# ES_Daisy_Seed2_DFM_EVAL_EURO_Rev2.net
KiCad netlist of a schematic drawn in EAGLE
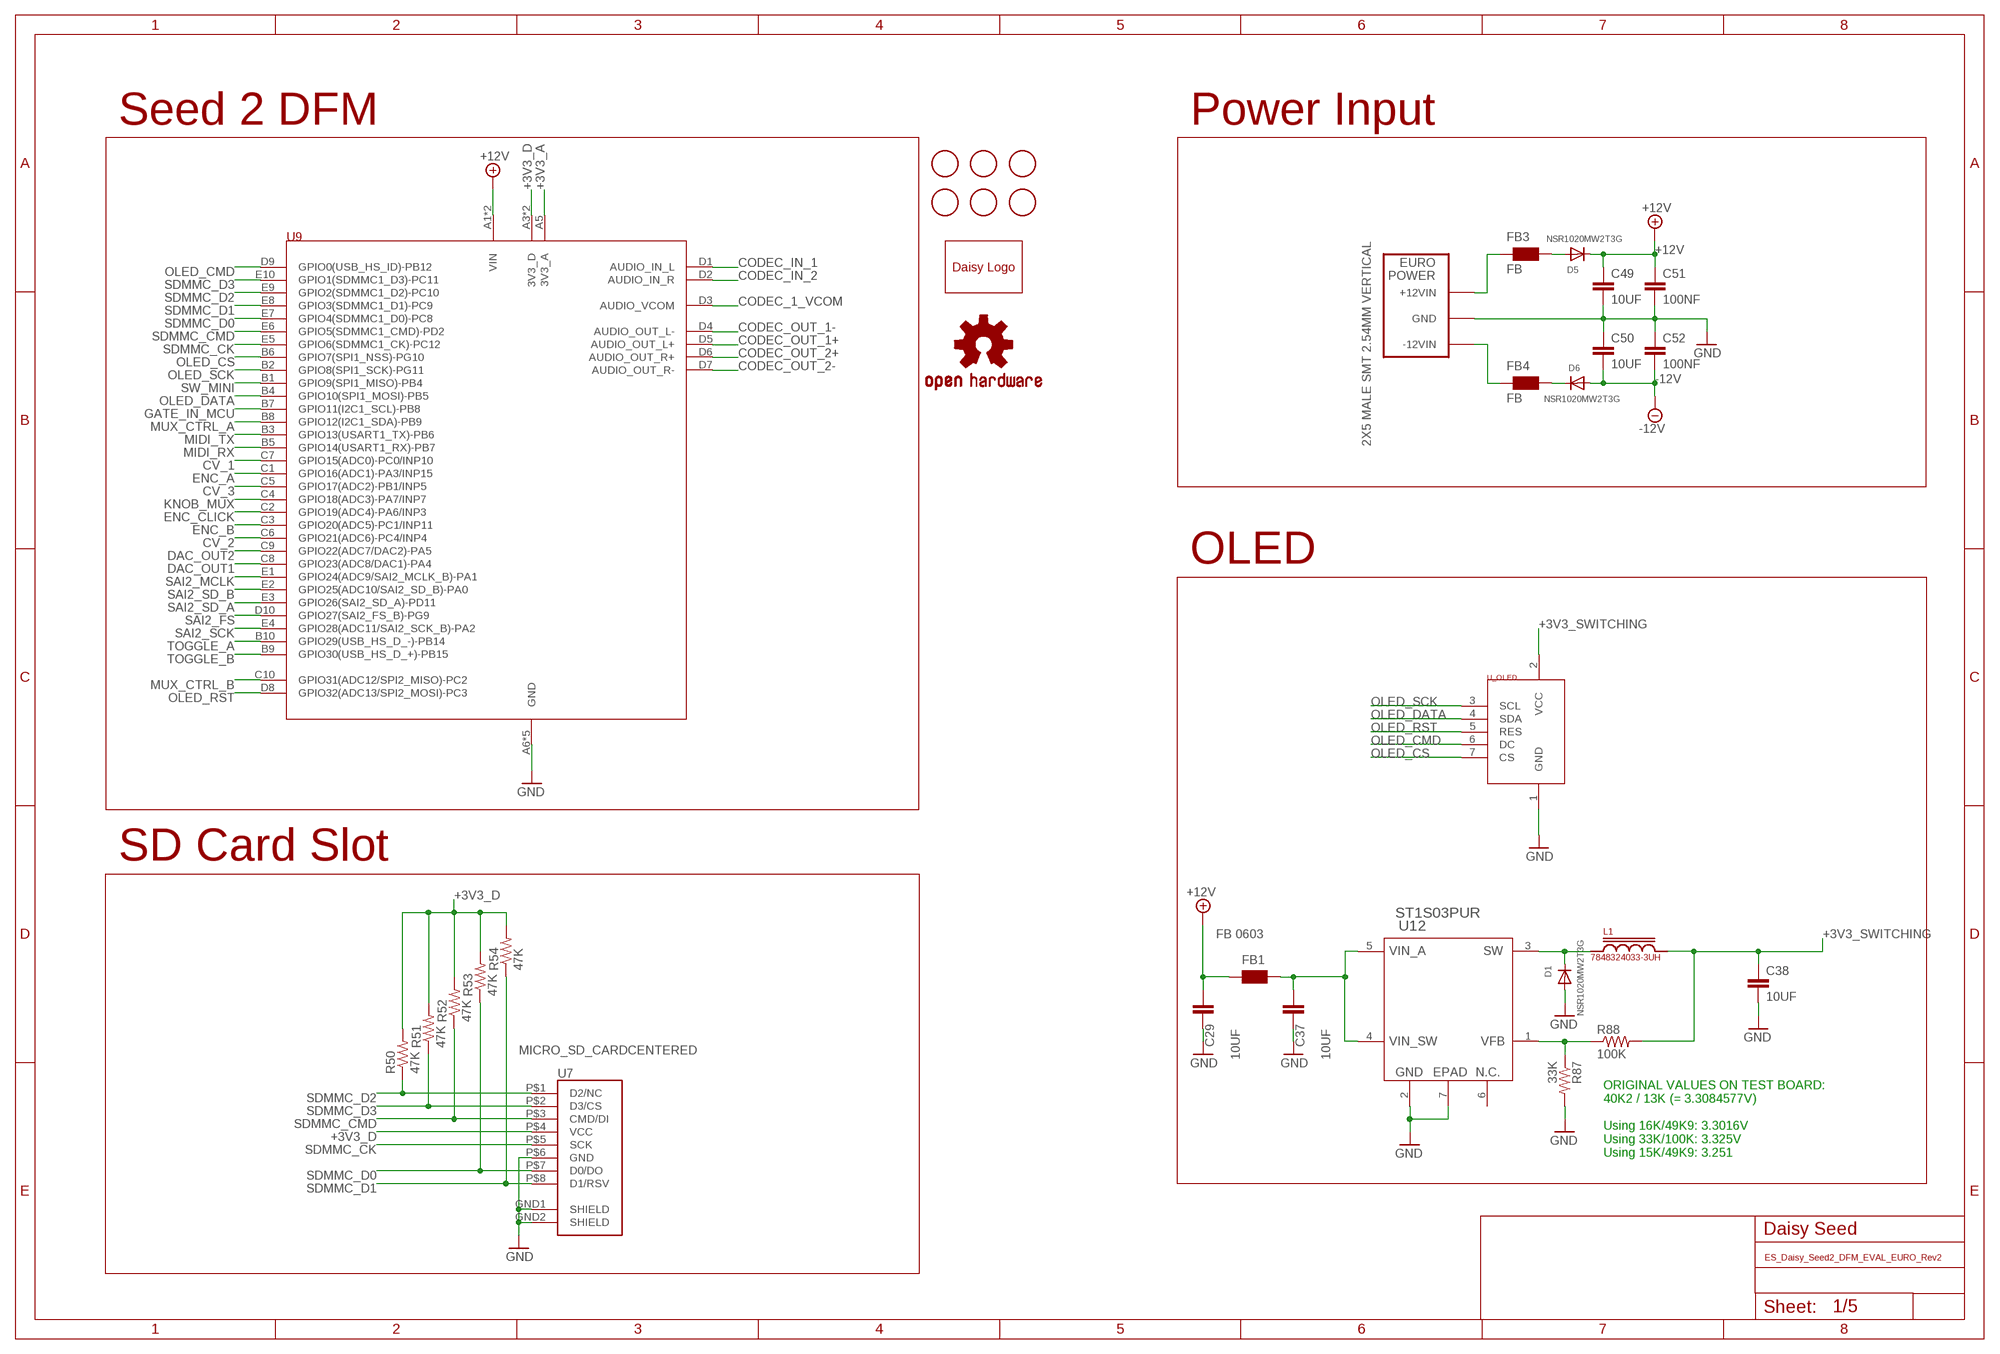
[diagram p0: schematic, sheet 1]
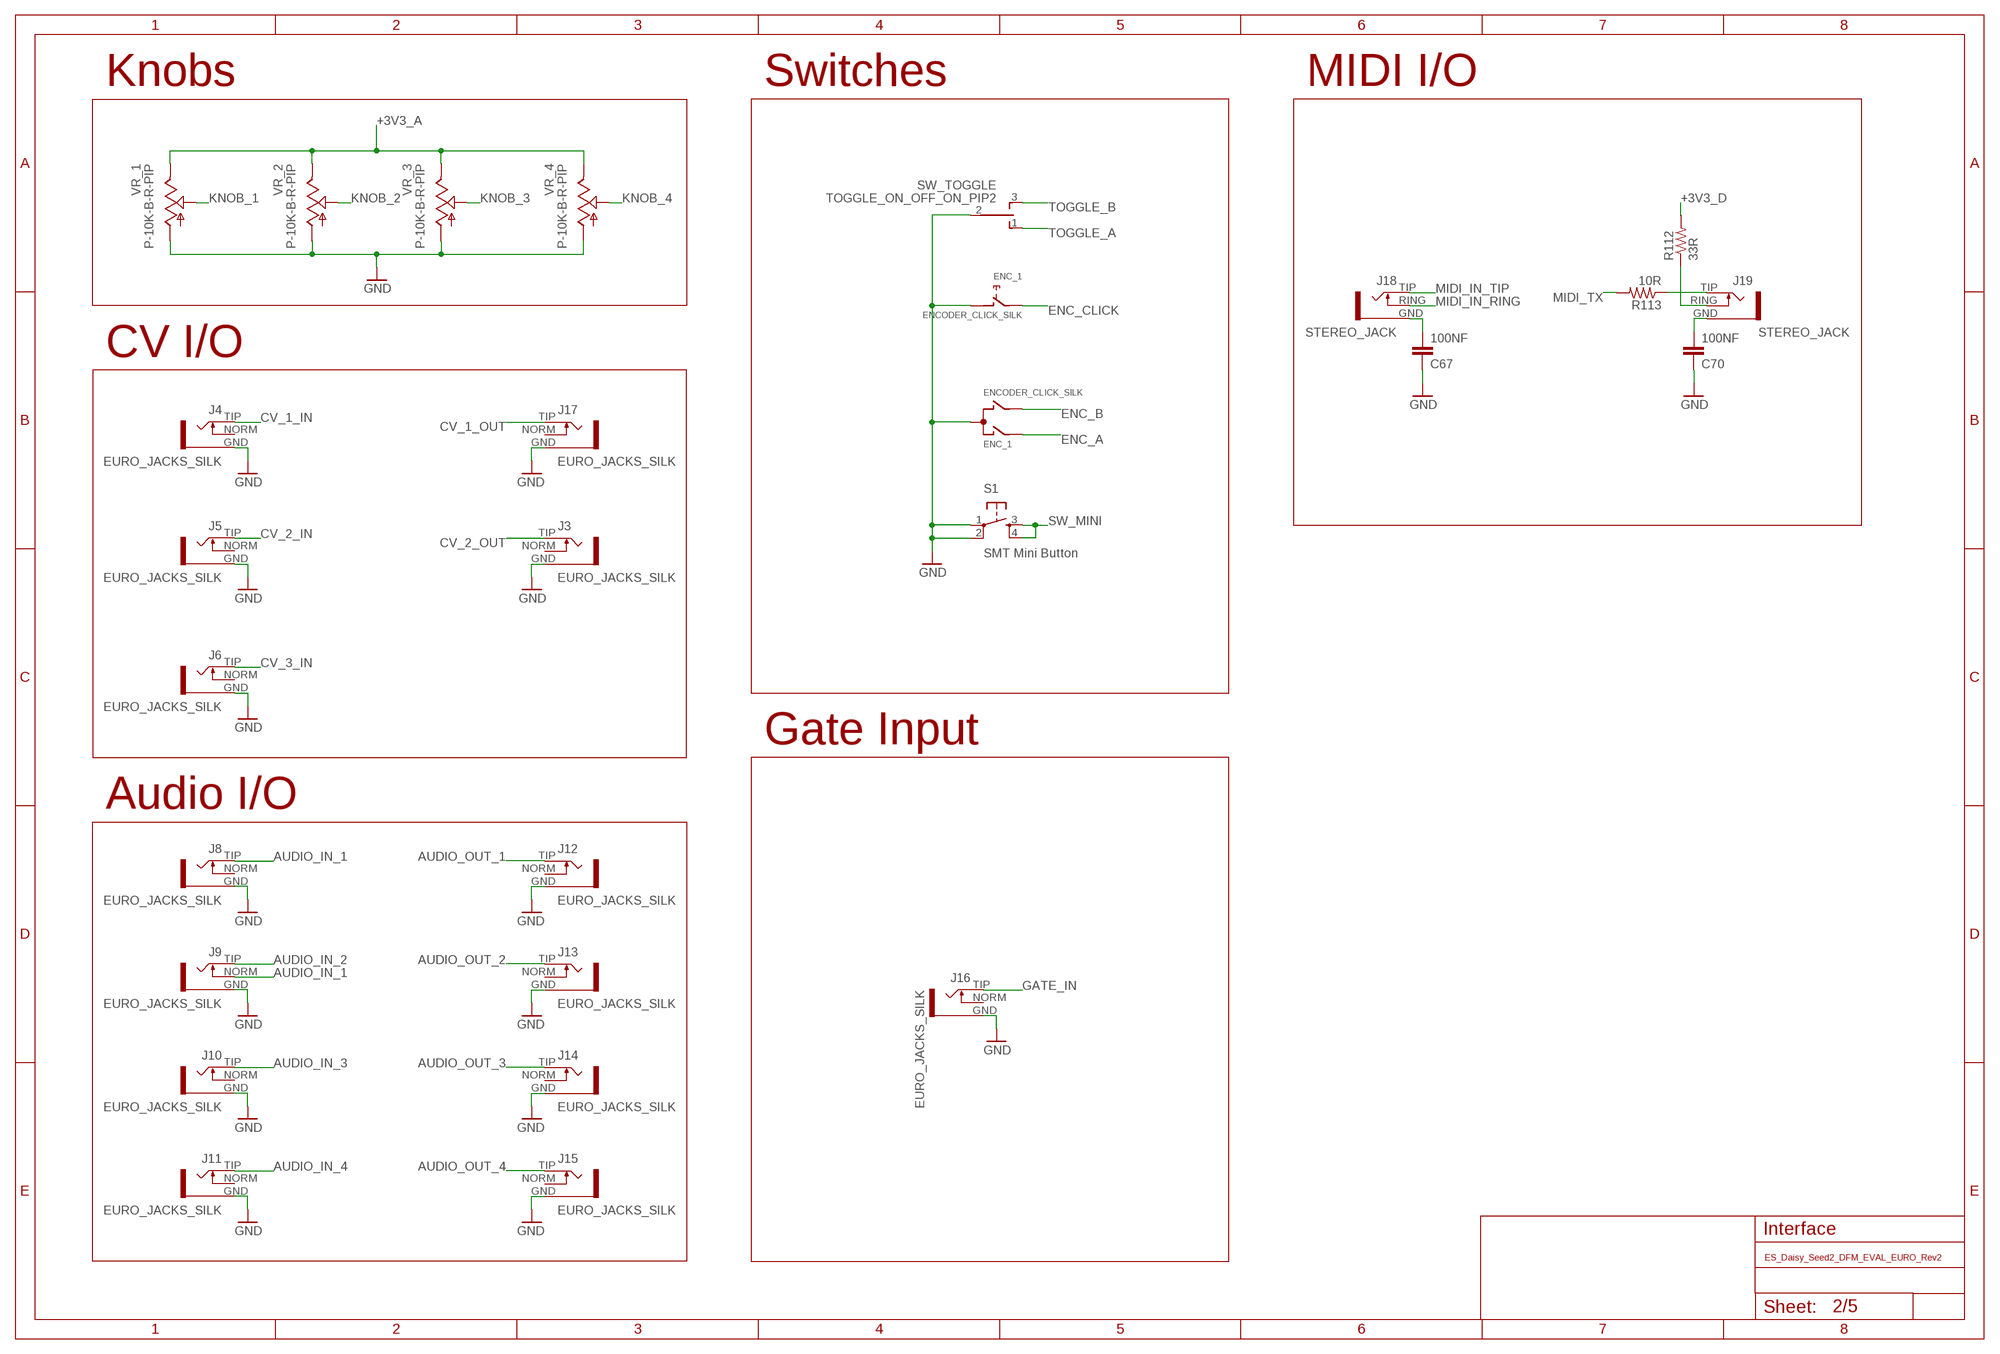
[diagram p1: schematic, sheet 2]
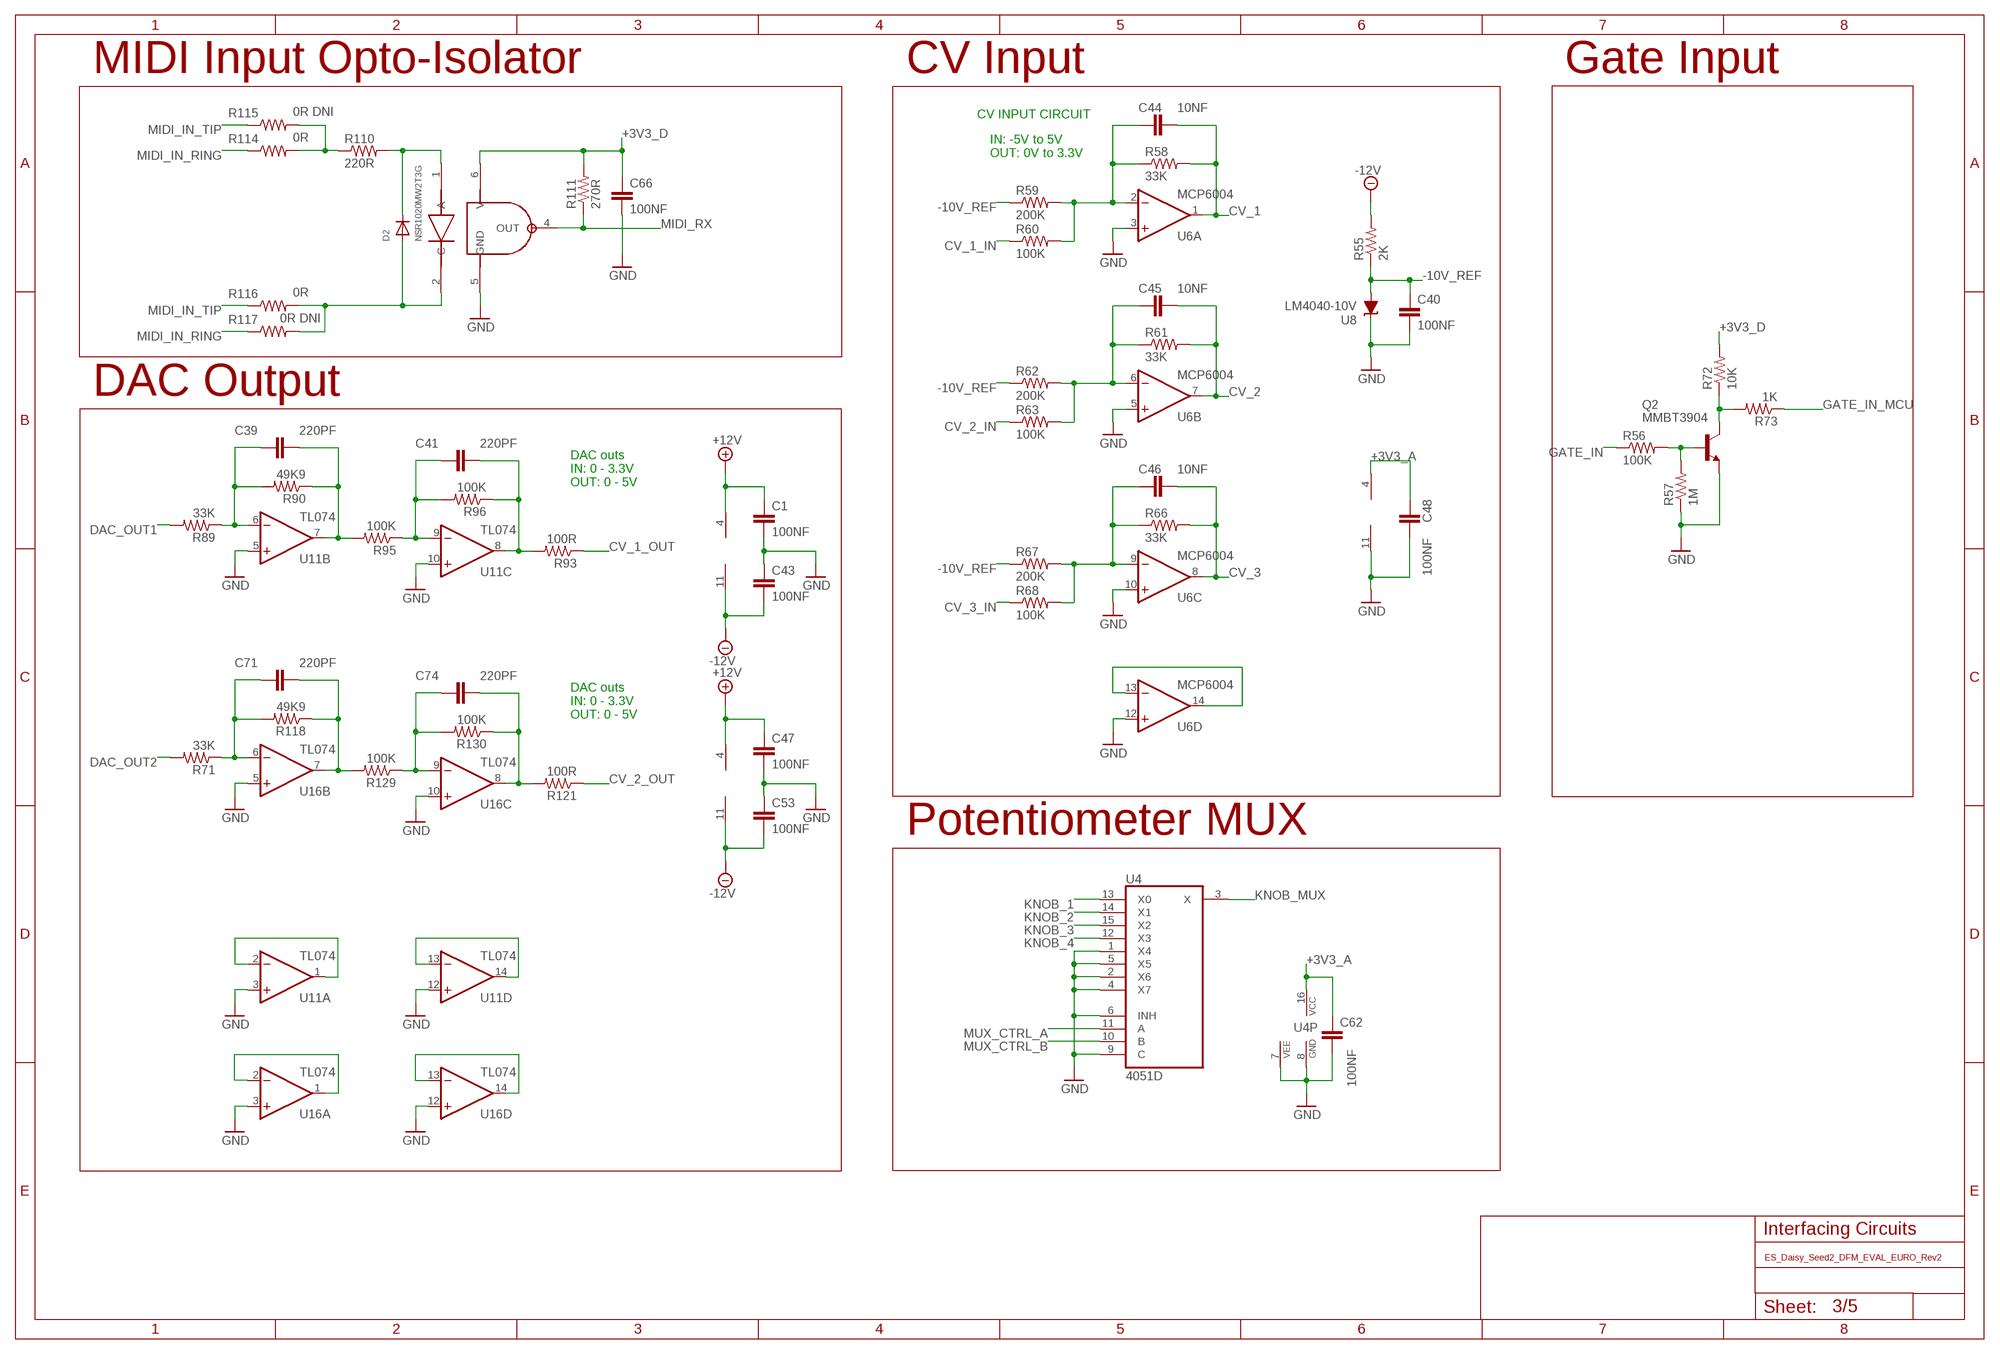
[diagram p2: schematic, sheet 3]
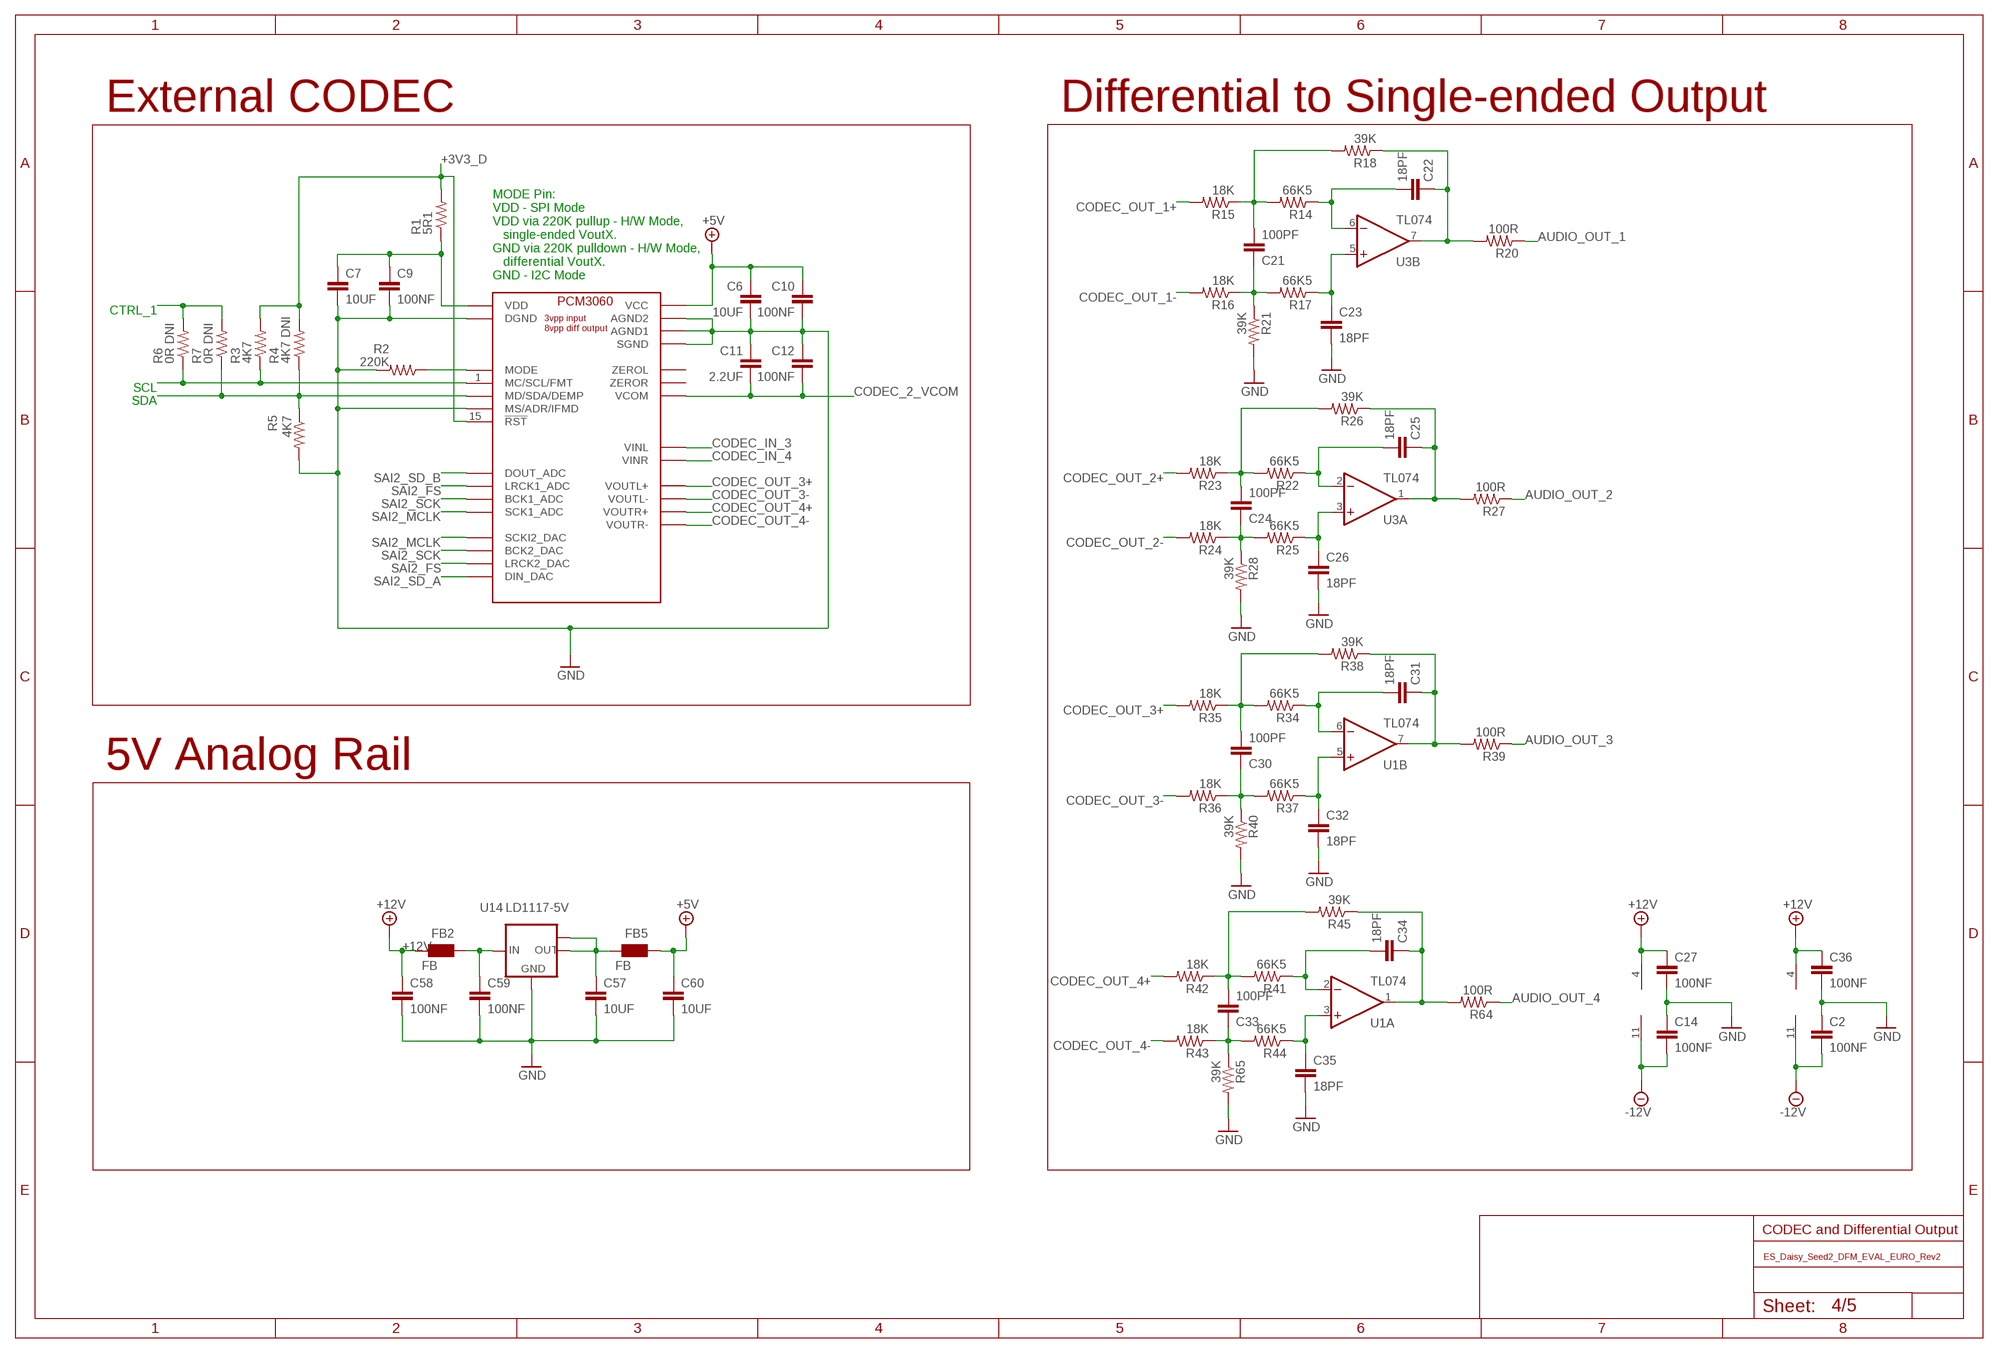
[diagram p3: schematic, sheet 4]
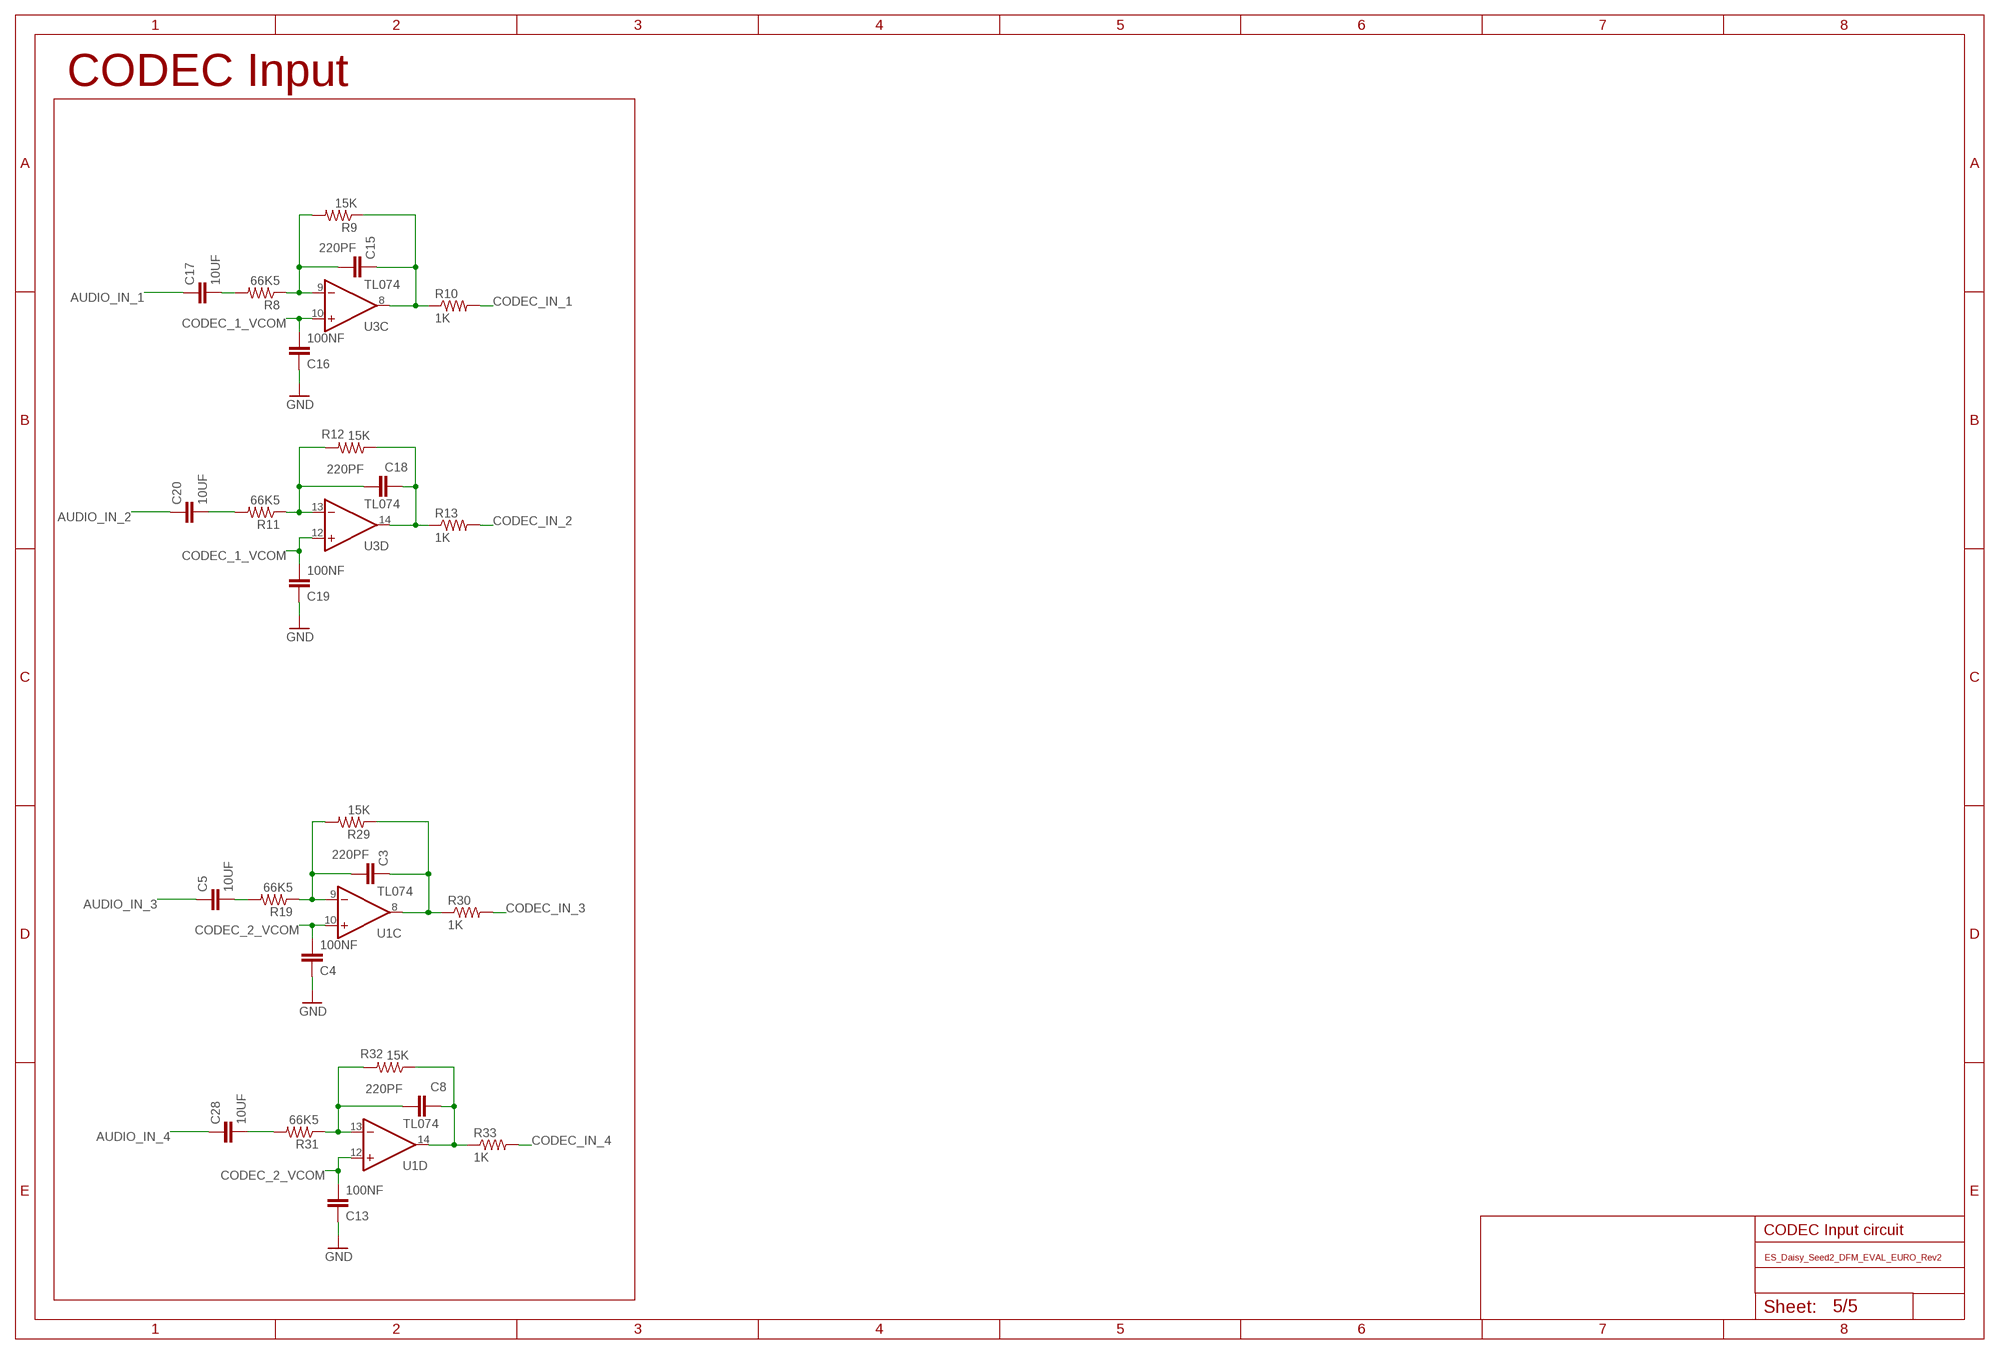
[diagram p4: schematic, sheet 5]

(export (version "E")
  (design (tool "Eeschema 10.0.6"))
  (components
    (comp (ref "C1")
      (value "100NF")
      (footprint "eagle-import:C0402")
      (libsource (lib "eagle-import") (part "C-EUC0402"))
    )
    (comp (ref "C39")
      (value "220PF")
      (footprint "eagle-import:C0603")
      (libsource (lib "eagle-import") (part "C-EUC0603"))
    )
    (comp (ref "C40")
      (value "100NF")
      (footprint "eagle-import:C0402")
      (libsource (lib "eagle-import") (part "C-EUC0402"))
    )
    (comp (ref "C41")
      (value "220PF")
      (footprint "eagle-import:C0603")
      (libsource (lib "eagle-import") (part "C-EUC0603"))
    )
    (comp (ref "C43")
      (value "100NF")
      (footprint "eagle-import:C0402")
      (libsource (lib "eagle-import") (part "C-EUC0402"))
    )
    (comp (ref "C44")
      (value "10NF")
      (footprint "eagle-import:C0603")
      (libsource (lib "eagle-import") (part "C-EUC0603"))
    )
    (comp (ref "C45")
      (value "10NF")
      (footprint "eagle-import:C0603")
      (libsource (lib "eagle-import") (part "C-EUC0603"))
    )
    (comp (ref "C46")
      (value "10NF")
      (footprint "eagle-import:C0603")
      (libsource (lib "eagle-import") (part "C-EUC0603"))
    )
    (comp (ref "C47")
      (value "100NF")
      (footprint "eagle-import:C0402")
      (libsource (lib "eagle-import") (part "C-EUC0402"))
    )
    (comp (ref "C48")
      (value "100NF")
      (footprint "eagle-import:C0402")
      (libsource (lib "eagle-import") (part "C-EUC0402"))
    )
    (comp (ref "C53")
      (value "100NF")
      (footprint "eagle-import:C0402")
      (libsource (lib "eagle-import") (part "C-EUC0402"))
    )
    (comp (ref "C62")
      (value "100NF")
      (footprint "eagle-import:C0402")
      (libsource (lib "eagle-import") (part "C-EUC0402"))
    )
    (comp (ref "C66")
      (value "100NF")
      (footprint "eagle-import:C0402")
      (libsource (lib "eagle-import") (part "C-EUC0402"))
    )
    (comp (ref "C71")
      (value "220PF")
      (footprint "eagle-import:C0603")
      (libsource (lib "eagle-import") (part "C-EUC0603"))
    )
    (comp (ref "C74")
      (value "220PF")
      (footprint "eagle-import:C0603")
      (libsource (lib "eagle-import") (part "C-EUC0603"))
    )
    (comp (ref "D2")
      (value "NSR1020MW2T3G")
      (footprint "eagle-import:SOD-323F")
      (libsource (lib "eagle-import") (part "DIODE_SOD-323F"))
    )
    (comp (ref "Q2")
      (value "MMBT3904")
      (footprint "eagle-import:SOT23-BEC")
      (libsource (lib "eagle-import") (part "NPNSOT23-BEC"))
    )
    (comp (ref "R55")
      (value "2K")
      (footprint "eagle-import:R0603")
      (libsource (lib "eagle-import") (part "R-US_R0603"))
    )
    (comp (ref "R56")
      (value "100K")
      (footprint "eagle-import:R0402")
      (libsource (lib "eagle-import") (part "R-US_R0402"))
    )
    (comp (ref "R57")
      (value "1M")
      (footprint "eagle-import:R0603")
      (libsource (lib "eagle-import") (part "R-US_R0603"))
    )
    (comp (ref "R58")
      (value "33K")
      (footprint "eagle-import:R0603")
      (libsource (lib "eagle-import") (part "R-US_R0603"))
    )
    (comp (ref "R59")
      (value "200K")
      (footprint "eagle-import:R0603")
      (libsource (lib "eagle-import") (part "R-US_R0603"))
    )
    (comp (ref "R60")
      (value "100K")
      (footprint "eagle-import:R0402")
      (libsource (lib "eagle-import") (part "R-US_R0402"))
    )
    (comp (ref "R61")
      (value "33K")
      (footprint "eagle-import:R0603")
      (libsource (lib "eagle-import") (part "R-US_R0603"))
    )
    (comp (ref "R62")
      (value "200K")
      (footprint "eagle-import:R0603")
      (libsource (lib "eagle-import") (part "R-US_R0603"))
    )
    (comp (ref "R63")
      (value "100K")
      (footprint "eagle-import:R0402")
      (libsource (lib "eagle-import") (part "R-US_R0402"))
    )
    (comp (ref "R66")
      (value "33K")
      (footprint "eagle-import:R0603")
      (libsource (lib "eagle-import") (part "R-US_R0603"))
    )
    (comp (ref "R67")
      (value "200K")
      (footprint "eagle-import:R0603")
      (libsource (lib "eagle-import") (part "R-US_R0603"))
    )
    (comp (ref "R68")
      (value "100K")
      (footprint "eagle-import:R0402")
      (libsource (lib "eagle-import") (part "R-US_R0402"))
    )
    (comp (ref "R71")
      (value "33K")
      (footprint "eagle-import:R0603")
      (libsource (lib "eagle-import") (part "R-US_R0603"))
    )
    (comp (ref "R72")
      (value "10K")
      (footprint "eagle-import:R0603")
      (libsource (lib "eagle-import") (part "R-US_R0603"))
    )
    (comp (ref "R73")
      (value "1K")
      (footprint "eagle-import:R0402")
      (libsource (lib "eagle-import") (part "R-US_R0402"))
    )
    (comp (ref "R89")
      (value "33K")
      (footprint "eagle-import:R0603")
      (libsource (lib "eagle-import") (part "R-US_R0603"))
    )
    (comp (ref "R90")
      (value "49K9")
      (footprint "eagle-import:R0603")
      (libsource (lib "eagle-import") (part "R-US_R0603"))
    )
    (comp (ref "R93")
      (value "100R")
      (footprint "eagle-import:R0603")
      (libsource (lib "eagle-import") (part "R-US_R0603"))
    )
    (comp (ref "R95")
      (value "100K")
      (footprint "eagle-import:R0402")
      (libsource (lib "eagle-import") (part "R-US_R0402"))
    )
    (comp (ref "R96")
      (value "100K")
      (footprint "eagle-import:R0402")
      (libsource (lib "eagle-import") (part "R-US_R0402"))
    )
    (comp (ref "R110")
      (value "220R")
      (footprint "eagle-import:R0603")
      (libsource (lib "eagle-import") (part "R-US_R0603"))
    )
    (comp (ref "R111")
      (value "270R")
      (footprint "eagle-import:R0603")
      (libsource (lib "eagle-import") (part "R-US_R0603"))
    )
    (comp (ref "R114")
      (value "0R")
      (footprint "eagle-import:R0603")
      (libsource (lib "eagle-import") (part "R-US_R0603"))
    )
    (comp (ref "R115")
      (value "0R DNI")
      (footprint "eagle-import:R0603")
      (libsource (lib "eagle-import") (part "R-US_R0603"))
    )
    (comp (ref "R116")
      (value "0R")
      (footprint "eagle-import:R0603")
      (libsource (lib "eagle-import") (part "R-US_R0603"))
    )
    (comp (ref "R117")
      (value "0R DNI")
      (footprint "eagle-import:R0603")
      (libsource (lib "eagle-import") (part "R-US_R0603"))
    )
    (comp (ref "R118")
      (value "49K9")
      (footprint "eagle-import:R0603")
      (libsource (lib "eagle-import") (part "R-US_R0603"))
    )
    (comp (ref "R121")
      (value "100R")
      (footprint "eagle-import:R0603")
      (libsource (lib "eagle-import") (part "R-US_R0603"))
    )
    (comp (ref "R129")
      (value "100K")
      (footprint "eagle-import:R0402")
      (libsource (lib "eagle-import") (part "R-US_R0402"))
    )
    (comp (ref "R130")
      (value "100K")
      (footprint "eagle-import:R0402")
      (libsource (lib "eagle-import") (part "R-US_R0402"))
    )
    (comp (ref "U4")
      (value "4051D")
      (footprint "eagle-import:SO-16")
      (libsource (lib "eagle-import") (part "4051D"))
    )
    (comp (ref "U6")
      (value "MCP6004")
      (footprint "eagle-import:TSSOP-14")
      (fields (field (name "MPN") "MCP6004T-E/ST"))
      (libsource (lib "eagle-import") (part "MCP6004_TSSOP-14"))
    )
    (comp (ref "U8")
      (value "LM4040-10V")
      (footprint "eagle-import:DBZ_R-PDSO-G3")
      (fields (field (name "MPN") "LM4041A12IDBZR"))
      (libsource (lib "eagle-import") (part "LM4040-10VDBZA12"))
    )
    (comp (ref "U11")
      (value "TL074")
      (footprint "eagle-import:TSSOP-14")
      (fields (field (name "MPN") "TL074CPWR"))
      (libsource (lib "eagle-import") (part "TL074_TSSOP-14"))
    )
    (comp (ref "U15")
      (value "OPTOISOLATOR_H11L1M")
      (footprint "eagle-import:DIL06_GULLWING")
      (fields (field (name "MPN") "H11L1SR2M"))
      (libsource (lib "eagle-import") (part "OPTOISOLATOR_H11L1M"))
    )
    (comp (ref "U16")
      (value "TL074")
      (footprint "eagle-import:TSSOP-14")
      (fields (field (name "MPN") "TL074CPWR"))
      (libsource (lib "eagle-import") (part "TL074_TSSOP-14"))
    )
    (comp (ref "C29")
      (value "10UF")
      (footprint "eagle-import:C0805")
      (libsource (lib "eagle-import") (part "C-EUC0805"))
    )
    (comp (ref "C37")
      (value "10UF")
      (footprint "eagle-import:C0805")
      (libsource (lib "eagle-import") (part "Electrosmith-Passives_29888544_C-EUC0805"))
    )
    (comp (ref "C38")
      (value "10UF")
      (footprint "eagle-import:C0805")
      (libsource (lib "eagle-import") (part "C-EUC0805"))
    )
    (comp (ref "C49")
      (value "10UF")
      (footprint "eagle-import:C0805")
      (libsource (lib "eagle-import") (part "C-EUC0805"))
    )
    (comp (ref "C50")
      (value "10UF")
      (footprint "eagle-import:C0805")
      (libsource (lib "eagle-import") (part "C-EUC0805"))
    )
    (comp (ref "C51")
      (value "100NF")
      (footprint "eagle-import:C0402")
      (libsource (lib "eagle-import") (part "C-EUC0402"))
    )
    (comp (ref "C52")
      (value "100NF")
      (footprint "eagle-import:C0402")
      (libsource (lib "eagle-import") (part "C-EUC0402"))
    )
    (comp (ref "D1")
      (value "NSR1020MW2T3G")
      (footprint "eagle-import:SOD-323F")
      (libsource (lib "eagle-import") (part "Electrosmith-Semiconductors_29887508_DIODE_SOD-323F"))
    )
    (comp (ref "D5")
      (value "NSR1020MW2T3G")
      (footprint "eagle-import:SOD-323F")
      (libsource (lib "eagle-import") (part "DIODE_SOD-323F"))
    )
    (comp (ref "D6")
      (value "NSR1020MW2T3G")
      (footprint "eagle-import:SOD-323F")
      (libsource (lib "eagle-import") (part "DIODE_SOD-323F"))
    )
    (comp (ref "FB1")
      (value "FB 0603")
      (footprint "eagle-import:WUERTH-ELEKTRONIK_0603")
      (libsource (lib "eagle-import") (part "FERRITE_BEAD_0603"))
    )
    (comp (ref "FB3")
      (value "FB")
      (footprint "eagle-import:WUERTH-ELEKTRONIK_0603")
      (libsource (lib "eagle-import") (part "FERRITE_BEAD_0603"))
    )
    (comp (ref "FB4")
      (value "FB")
      (footprint "eagle-import:WUERTH-ELEKTRONIK_0603")
      (libsource (lib "eagle-import") (part "FERRITE_BEAD_0603"))
    )
    (comp (ref "FD1")
      (value "FIDUCIAL")
      (footprint "eagle-import:FIDUCIAL_1MM")
      (libsource (lib "eagle-import") (part "FIDUCIAL"))
    )
    (comp (ref "FD2")
      (value "FIDUCIAL")
      (footprint "eagle-import:FIDUCIAL_1MM")
      (libsource (lib "eagle-import") (part "FIDUCIAL"))
    )
    (comp (ref "FD3")
      (value "FIDUCIAL")
      (footprint "eagle-import:FIDUCIAL_1MM")
      (libsource (lib "eagle-import") (part "FIDUCIAL"))
    )
    (comp (ref "FD4")
      (value "FIDUCIAL")
      (footprint "eagle-import:FIDUCIAL_1MM")
      (libsource (lib "eagle-import") (part "FIDUCIAL"))
    )
    (comp (ref "FD5")
      (value "FIDUCIAL")
      (footprint "eagle-import:FIDUCIAL_1MM")
      (libsource (lib "eagle-import") (part "FIDUCIAL"))
    )
    (comp (ref "FD6")
      (value "FIDUCIAL")
      (footprint "eagle-import:FIDUCIAL_1MM")
      (libsource (lib "eagle-import") (part "FIDUCIAL"))
    )
    (comp (ref "L1")
      (value "7848324033-3UH")
      (footprint "eagle-import:I1008")
      (fields (field (name "MPN") "AIML-1008HC-3R3M-T"))
      (libsource (lib "eagle-import") (part "INDUCTOR1008"))
    )
    (comp (ref "LOGO1")
      (value "OSHW-LOGO")
      (footprint "eagle-import:OSHW-LOGO-L_TEXT")
      (libsource (lib "eagle-import") (part "OSHW-LOGO"))
    )
    (comp (ref "P1")
      (value "2X5 MALE SMT 2.54MM VERTICAL")
      (footprint "eagle-import:EURORACK_POWER_SMT")
      (fields (field (name "MANF") "FCI") (field (name "MPN") "PH2-10-MTA-SMT-PP-T/R"))
      (libsource (lib "eagle-import") (part "EURORACK_POWERSMT"))
    )
    (comp (ref "R50")
      (value "47K")
      (footprint "eagle-import:R0603")
      (libsource (lib "eagle-import") (part "R-US_R0603"))
    )
    (comp (ref "R51")
      (value "47K")
      (footprint "eagle-import:R0603")
      (libsource (lib "eagle-import") (part "R-US_R0603"))
    )
    (comp (ref "R52")
      (value "47K")
      (footprint "eagle-import:R0603")
      (libsource (lib "eagle-import") (part "R-US_R0603"))
    )
    (comp (ref "R53")
      (value "47K")
      (footprint "eagle-import:R0603")
      (libsource (lib "eagle-import") (part "R-US_R0603"))
    )
    (comp (ref "R54")
      (value "47K")
      (footprint "eagle-import:R0603")
      (libsource (lib "eagle-import") (part "R-US_R0603"))
    )
    (comp (ref "R87")
      (value "33K")
      (footprint "eagle-import:R0603")
      (libsource (lib "eagle-import") (part "R-US_R0603"))
    )
    (comp (ref "R88")
      (value "100K")
      (footprint "eagle-import:R0402")
      (libsource (lib "eagle-import") (part "R-US_R0402"))
    )
    (comp (ref "U$5")
      (value "DAISYLOGO")
      (footprint "eagle-import:ES_DAISY_LOGO_1")
      (libsource (lib "eagle-import") (part "DAISYLOGO"))
    )
    (comp (ref "U7")
      (value "MICRO_SD_CARDCENTERED")
      (footprint "eagle-import:VERT_MICROSD_CENTERED")
      (libsource (lib "eagle-import") (part "MICRO_SD_CARDCENTERED"))
    )
    (comp (ref "U9")
      (value "ES_DAISY_SEED2_DFM_REV1\"\"")
      (footprint "eagle-import:ES_DAISY_SEED2_DFM_REV1")
      (libsource (lib "eagle-import") (part "ES_DAISY_SEED2_DFM_REV1{dblquote}{dblquote}"))
    )
    (comp (ref "U12")
      (value "ST1S03PUR")
      (footprint "eagle-import:DFN06_3X3_STM")
      (fields (field (name "COPYRIGHT") "Copyright (C) 2021 Ultra Librarian. All rights reserved."))
      (libsource (lib "eagle-import") (part "ST1S03PUR"))
    )
    (comp (ref "U_OLED")
      (value "OLED_DISPLAY")
      (footprint "eagle-import:ER-OLEDM015-2")
      (fields (field (name "MPN") "ER-OLEDM015-2W-SPI-I2C"))
      (libsource (lib "eagle-import") (part "OLED_DISPLAY"))
    )
    (comp (ref "C67")
      (value "100NF")
      (footprint "eagle-import:C0402")
      (libsource (lib "eagle-import") (part "C-EUC0402"))
    )
    (comp (ref "C70")
      (value "100NF")
      (footprint "eagle-import:C0402")
      (libsource (lib "eagle-import") (part "C-EUC0402"))
    )
    (comp (ref "ENC_1")
      (value "ENCODER_CLICK_SILK")
      (footprint "eagle-import:PEC11_SILK")
      (libsource (lib "eagle-import") (part "ENCODERSILK_CLICK_"))
    )
    (comp (ref "J3")
      (value "EURO_JACKS_SILK")
      (footprint "eagle-import:S_JACK_SILK")
      (libsource (lib "eagle-import") (part "EURO_JACKS_SILK"))
    )
    (comp (ref "J4")
      (value "EURO_JACKS_SILK")
      (footprint "eagle-import:S_JACK_SILK")
      (libsource (lib "eagle-import") (part "EURO_JACKS_SILK"))
    )
    (comp (ref "J5")
      (value "EURO_JACKS_SILK")
      (footprint "eagle-import:S_JACK_SILK")
      (libsource (lib "eagle-import") (part "EURO_JACKS_SILK"))
    )
    (comp (ref "J6")
      (value "EURO_JACKS_SILK")
      (footprint "eagle-import:S_JACK_SILK")
      (libsource (lib "eagle-import") (part "EURO_JACKS_SILK"))
    )
    (comp (ref "J8")
      (value "EURO_JACKS_SILK")
      (footprint "eagle-import:S_JACK_SILK")
      (libsource (lib "eagle-import") (part "EURO_JACKS_SILK"))
    )
    (comp (ref "J9")
      (value "EURO_JACKS_SILK")
      (footprint "eagle-import:S_JACK_SILK")
      (libsource (lib "eagle-import") (part "EURO_JACKS_SILK"))
    )
    (comp (ref "J10")
      (value "EURO_JACKS_SILK")
      (footprint "eagle-import:S_JACK_SILK")
      (libsource (lib "eagle-import") (part "EURO_JACKS_SILK"))
    )
    (comp (ref "J11")
      (value "EURO_JACKS_SILK")
      (footprint "eagle-import:S_JACK_SILK")
      (libsource (lib "eagle-import") (part "EURO_JACKS_SILK"))
    )
    (comp (ref "J12")
      (value "EURO_JACKS_SILK")
      (footprint "eagle-import:S_JACK_SILK")
      (libsource (lib "eagle-import") (part "EURO_JACKS_SILK"))
    )
    (comp (ref "J13")
      (value "EURO_JACKS_SILK")
      (footprint "eagle-import:S_JACK_SILK")
      (libsource (lib "eagle-import") (part "EURO_JACKS_SILK"))
    )
    (comp (ref "J14")
      (value "EURO_JACKS_SILK")
      (footprint "eagle-import:S_JACK_SILK")
      (libsource (lib "eagle-import") (part "EURO_JACKS_SILK"))
    )
    (comp (ref "J15")
      (value "EURO_JACKS_SILK")
      (footprint "eagle-import:S_JACK_SILK")
      (libsource (lib "eagle-import") (part "EURO_JACKS_SILK"))
    )
    (comp (ref "J16")
      (value "EURO_JACKS_SILK")
      (footprint "eagle-import:S_JACK_SILK")
      (libsource (lib "eagle-import") (part "EURO_JACKS_SILK"))
    )
    (comp (ref "J17")
      (value "EURO_JACKS_SILK")
      (footprint "eagle-import:S_JACK_SILK")
      (libsource (lib "eagle-import") (part "EURO_JACKS_SILK"))
    )
    (comp (ref "J18")
      (value "STEREO_JACK")
      (footprint "eagle-import:STEREO_JACK_3.5MM")
      (libsource (lib "eagle-import") (part "STEREO_JACK"))
    )
    (comp (ref "J19")
      (value "STEREO_JACK")
      (footprint "eagle-import:STEREO_JACK_3.5MM")
      (libsource (lib "eagle-import") (part "STEREO_JACK"))
    )
    (comp (ref "R112")
      (value "33R")
      (footprint "eagle-import:R0603")
      (libsource (lib "eagle-import") (part "R-US_R0603"))
    )
    (comp (ref "R113")
      (value "10R")
      (footprint "eagle-import:R0603")
      (libsource (lib "eagle-import") (part "R-US_R0603"))
    )
    (comp (ref "S1")
      (value "SMT Mini Button")
      (footprint "eagle-import:TL3301SPF160QJ")
      (fields (field (name "MPN") "TL3301SPF160QJ"))
      (libsource (lib "eagle-import") (part "TAC_SWITCH_SMT"))
    )
    (comp (ref "SW_TOGGLE")
      (value "TOGGLE_ON_OFF_ON_PIP2")
      (footprint "eagle-import:TOGGLE_SILK_PIP3")
      (libsource (lib "eagle-import") (part "TOGGLE_ON_OFF_ON_PIP2"))
    )
    (comp (ref "VR_1")
      (value "P-10K-B-R-PIP")
      (footprint "eagle-import:9MM_SNAP-IN_POT_SILK_PIP")
      (libsource (lib "eagle-import") (part "POT_9MM_SNAP-IN__SILK_PIP"))
    )
    (comp (ref "VR_2")
      (value "P-10K-B-R-PIP")
      (footprint "eagle-import:9MM_SNAP-IN_POT_SILK_PIP")
      (libsource (lib "eagle-import") (part "POT_9MM_SNAP-IN__SILK_PIP"))
    )
    (comp (ref "VR_3")
      (value "P-10K-B-R-PIP")
      (footprint "eagle-import:9MM_SNAP-IN_POT_SILK_PIP")
      (libsource (lib "eagle-import") (part "POT_9MM_SNAP-IN__SILK_PIP"))
    )
    (comp (ref "VR_4")
      (value "P-10K-B-R-PIP")
      (footprint "eagle-import:9MM_SNAP-IN_POT_SILK_PIP")
      (libsource (lib "eagle-import") (part "POT_9MM_SNAP-IN__SILK_PIP"))
    )
    (comp (ref "C3")
      (value "220PF")
      (footprint "eagle-import:C0603")
      (libsource (lib "eagle-import") (part "C-EUC0603"))
    )
    (comp (ref "C4")
      (value "100NF")
      (footprint "eagle-import:C0402")
      (libsource (lib "eagle-import") (part "C-EUC0402"))
    )
    (comp (ref "C5")
      (value "10UF")
      (footprint "eagle-import:C0805")
      (libsource (lib "eagle-import") (part "C-EUC0805"))
    )
    (comp (ref "C8")
      (value "220PF")
      (footprint "eagle-import:C0603")
      (libsource (lib "eagle-import") (part "C-EUC0603"))
    )
    (comp (ref "C13")
      (value "100NF")
      (footprint "eagle-import:C0402")
      (libsource (lib "eagle-import") (part "C-EUC0402"))
    )
    (comp (ref "C15")
      (value "220PF")
      (footprint "eagle-import:C0603")
      (libsource (lib "eagle-import") (part "C-EUC0603"))
    )
    (comp (ref "C16")
      (value "100NF")
      (footprint "eagle-import:C0402")
      (libsource (lib "eagle-import") (part "C-EUC0402"))
    )
    (comp (ref "C17")
      (value "10UF")
      (footprint "eagle-import:C0805")
      (libsource (lib "eagle-import") (part "C-EUC0805"))
    )
    (comp (ref "C18")
      (value "220PF")
      (footprint "eagle-import:C0603")
      (libsource (lib "eagle-import") (part "C-EUC0603"))
    )
    (comp (ref "C19")
      (value "100NF")
      (footprint "eagle-import:C0402")
      (libsource (lib "eagle-import") (part "C-EUC0402"))
    )
    (comp (ref "C20")
      (value "10UF")
      (footprint "eagle-import:C0805")
      (libsource (lib "eagle-import") (part "C-EUC0805"))
    )
    (comp (ref "C28")
      (value "10UF")
      (footprint "eagle-import:C0805")
      (libsource (lib "eagle-import") (part "C-EUC0805"))
    )
    (comp (ref "R8")
      (value "66K5")
      (footprint "eagle-import:R0603")
      (libsource (lib "eagle-import") (part "R-US_R0603"))
    )
    (comp (ref "R9")
      (value "15K")
      (footprint "eagle-import:R0603")
      (libsource (lib "eagle-import") (part "R-US_R0603"))
    )
    (comp (ref "R10")
      (value "1K")
      (footprint "eagle-import:R0402")
      (libsource (lib "eagle-import") (part "R-US_R0402"))
    )
    (comp (ref "R11")
      (value "66K5")
      (footprint "eagle-import:R0603")
      (libsource (lib "eagle-import") (part "R-US_R0603"))
    )
    (comp (ref "R12")
      (value "15K")
      (footprint "eagle-import:R0603")
      (libsource (lib "eagle-import") (part "R-US_R0603"))
    )
    (comp (ref "R13")
      (value "1K")
      (footprint "eagle-import:R0402")
      (libsource (lib "eagle-import") (part "R-US_R0402"))
    )
    (comp (ref "R19")
      (value "66K5")
      (footprint "eagle-import:R0603")
      (libsource (lib "eagle-import") (part "R-US_R0603"))
    )
    (comp (ref "R29")
      (value "15K")
      (footprint "eagle-import:R0603")
      (libsource (lib "eagle-import") (part "R-US_R0603"))
    )
    (comp (ref "R30")
      (value "1K")
      (footprint "eagle-import:R0402")
      (libsource (lib "eagle-import") (part "R-US_R0402"))
    )
    (comp (ref "R31")
      (value "66K5")
      (footprint "eagle-import:R0603")
      (libsource (lib "eagle-import") (part "R-US_R0603"))
    )
    (comp (ref "R32")
      (value "15K")
      (footprint "eagle-import:R0603")
      (libsource (lib "eagle-import") (part "R-US_R0603"))
    )
    (comp (ref "R33")
      (value "1K")
      (footprint "eagle-import:R0402")
      (libsource (lib "eagle-import") (part "R-US_R0402"))
    )
    (comp (ref "U1")
      (value "TL074")
      (footprint "eagle-import:TSSOP-14")
      (fields (field (name "MPN") "TL074CPWR"))
      (libsource (lib "eagle-import") (part "TL074_TSSOP-14"))
    )
    (comp (ref "U3")
      (value "TL074")
      (footprint "eagle-import:TSSOP-14")
      (fields (field (name "MPN") "TL074CPWR"))
      (libsource (lib "eagle-import") (part "TL074_TSSOP-14"))
    )
    (comp (ref "C2")
      (value "100NF")
      (footprint "eagle-import:C0402")
      (libsource (lib "eagle-import") (part "C-EUC0402"))
    )
    (comp (ref "C6")
      (value "10UF")
      (footprint "eagle-import:C0805")
      (libsource (lib "eagle-import") (part "C-EUC0805"))
    )
    (comp (ref "C7")
      (value "10UF")
      (footprint "eagle-import:C0805")
      (libsource (lib "eagle-import") (part "C-EUC0805"))
    )
    (comp (ref "C9")
      (value "100NF")
      (footprint "eagle-import:C0402")
      (libsource (lib "eagle-import") (part "C-EUC0402"))
    )
    (comp (ref "C10")
      (value "100NF")
      (footprint "eagle-import:C0402")
      (libsource (lib "eagle-import") (part "C-EUC0402"))
    )
    (comp (ref "C11")
      (value "2.2UF")
      (footprint "eagle-import:C0603")
      (libsource (lib "eagle-import") (part "C-EUC0603"))
    )
    (comp (ref "C12")
      (value "100NF")
      (footprint "eagle-import:C0402")
      (libsource (lib "eagle-import") (part "C-EUC0402"))
    )
    (comp (ref "C14")
      (value "100NF")
      (footprint "eagle-import:C0402")
      (libsource (lib "eagle-import") (part "C-EUC0402"))
    )
    (comp (ref "C21")
      (value "100PF")
      (footprint "eagle-import:C0603")
      (libsource (lib "eagle-import") (part "C-EUC0603"))
    )
    (comp (ref "C22")
      (value "18PF")
      (footprint "eagle-import:C0603")
      (libsource (lib "eagle-import") (part "C-EUC0603"))
    )
    (comp (ref "C23")
      (value "18PF")
      (footprint "eagle-import:C0603")
      (libsource (lib "eagle-import") (part "C-EUC0603"))
    )
    (comp (ref "C24")
      (value "100PF")
      (footprint "eagle-import:C0603")
      (libsource (lib "eagle-import") (part "C-EUC0603"))
    )
    (comp (ref "C25")
      (value "18PF")
      (footprint "eagle-import:C0603")
      (libsource (lib "eagle-import") (part "C-EUC0603"))
    )
    (comp (ref "C26")
      (value "18PF")
      (footprint "eagle-import:C0603")
      (libsource (lib "eagle-import") (part "C-EUC0603"))
    )
    (comp (ref "C27")
      (value "100NF")
      (footprint "eagle-import:C0402")
      (libsource (lib "eagle-import") (part "C-EUC0402"))
    )
    (comp (ref "C30")
      (value "100PF")
      (footprint "eagle-import:C0603")
      (libsource (lib "eagle-import") (part "C-EUC0603"))
    )
    (comp (ref "C31")
      (value "18PF")
      (footprint "eagle-import:C0603")
      (libsource (lib "eagle-import") (part "C-EUC0603"))
    )
    (comp (ref "C32")
      (value "18PF")
      (footprint "eagle-import:C0603")
      (libsource (lib "eagle-import") (part "C-EUC0603"))
    )
    (comp (ref "C33")
      (value "100PF")
      (footprint "eagle-import:C0603")
      (libsource (lib "eagle-import") (part "C-EUC0603"))
    )
    (comp (ref "C34")
      (value "18PF")
      (footprint "eagle-import:C0603")
      (libsource (lib "eagle-import") (part "C-EUC0603"))
    )
    (comp (ref "C35")
      (value "18PF")
      (footprint "eagle-import:C0603")
      (libsource (lib "eagle-import") (part "C-EUC0603"))
    )
    (comp (ref "C36")
      (value "100NF")
      (footprint "eagle-import:C0402")
      (libsource (lib "eagle-import") (part "C-EUC0402"))
    )
    (comp (ref "C57")
      (value "10UF")
      (footprint "eagle-import:C0805")
      (libsource (lib "eagle-import") (part "C-EUC0805"))
    )
    (comp (ref "C58")
      (value "100NF")
      (footprint "eagle-import:C0402")
      (libsource (lib "eagle-import") (part "C-EUC0402"))
    )
    (comp (ref "C59")
      (value "100NF")
      (footprint "eagle-import:C0402")
      (libsource (lib "eagle-import") (part "C-EUC0402"))
    )
    (comp (ref "C60")
      (value "10UF")
      (footprint "eagle-import:C0805")
      (libsource (lib "eagle-import") (part "C-EUC0805"))
    )
    (comp (ref "FB2")
      (value "FB")
      (footprint "eagle-import:WUERTH-ELEKTRONIK_0603")
      (libsource (lib "eagle-import") (part "FERRITE_BEAD_0603"))
    )
    (comp (ref "FB5")
      (value "FB")
      (footprint "eagle-import:WUERTH-ELEKTRONIK_0603")
      (libsource (lib "eagle-import") (part "FERRITE_BEAD_0603"))
    )
    (comp (ref "R1")
      (value "5R1")
      (footprint "eagle-import:R0603")
      (libsource (lib "eagle-import") (part "R-US_R0603"))
    )
    (comp (ref "R2")
      (value "220K")
      (footprint "eagle-import:R0603")
      (libsource (lib "eagle-import") (part "R-US_R0603"))
    )
    (comp (ref "R3")
      (value "4K7")
      (footprint "eagle-import:R0603")
      (libsource (lib "eagle-import") (part "R-US_R0603"))
    )
    (comp (ref "R4")
      (value "4K7 DNI")
      (footprint "eagle-import:R0603")
      (libsource (lib "eagle-import") (part "R-US_R0603"))
    )
    (comp (ref "R5")
      (value "4K7")
      (footprint "eagle-import:R0603")
      (libsource (lib "eagle-import") (part "R-US_R0603"))
    )
    (comp (ref "R6")
      (value "0R DNI")
      (footprint "eagle-import:R0603")
      (libsource (lib "eagle-import") (part "R-US_R0603"))
    )
    (comp (ref "R7")
      (value "0R DNI")
      (footprint "eagle-import:R0603")
      (libsource (lib "eagle-import") (part "R-US_R0603"))
    )
    (comp (ref "R14")
      (value "66K5")
      (footprint "eagle-import:R0603")
      (libsource (lib "eagle-import") (part "R-US_R0603"))
    )
    (comp (ref "R15")
      (value "18K")
      (footprint "eagle-import:R0603")
      (libsource (lib "eagle-import") (part "R-US_R0603"))
    )
    (comp (ref "R16")
      (value "18K")
      (footprint "eagle-import:R0603")
      (libsource (lib "eagle-import") (part "R-US_R0603"))
    )
    (comp (ref "R17")
      (value "66K5")
      (footprint "eagle-import:R0603")
      (libsource (lib "eagle-import") (part "R-US_R0603"))
    )
    (comp (ref "R18")
      (value "39K")
      (footprint "eagle-import:R0603")
      (libsource (lib "eagle-import") (part "R-US_R0603"))
    )
    (comp (ref "R20")
      (value "100R")
      (footprint "eagle-import:R0603")
      (libsource (lib "eagle-import") (part "R-US_R0603"))
    )
    (comp (ref "R21")
      (value "39K")
      (footprint "eagle-import:R0603")
      (libsource (lib "eagle-import") (part "R-US_R0603"))
    )
    (comp (ref "R22")
      (value "66K5")
      (footprint "eagle-import:R0603")
      (libsource (lib "eagle-import") (part "R-US_R0603"))
    )
    (comp (ref "R23")
      (value "18K")
      (footprint "eagle-import:R0603")
      (libsource (lib "eagle-import") (part "R-US_R0603"))
    )
    (comp (ref "R24")
      (value "18K")
      (footprint "eagle-import:R0603")
      (libsource (lib "eagle-import") (part "R-US_R0603"))
    )
    (comp (ref "R25")
      (value "66K5")
      (footprint "eagle-import:R0603")
      (libsource (lib "eagle-import") (part "R-US_R0603"))
    )
    (comp (ref "R26")
      (value "39K")
      (footprint "eagle-import:R0603")
      (libsource (lib "eagle-import") (part "R-US_R0603"))
    )
    (comp (ref "R27")
      (value "100R")
      (footprint "eagle-import:R0603")
      (libsource (lib "eagle-import") (part "R-US_R0603"))
    )
    (comp (ref "R28")
      (value "39K")
      (footprint "eagle-import:R0603")
      (libsource (lib "eagle-import") (part "R-US_R0603"))
    )
    (comp (ref "R34")
      (value "66K5")
      (footprint "eagle-import:R0603")
      (libsource (lib "eagle-import") (part "R-US_R0603"))
    )
    (comp (ref "R35")
      (value "18K")
      (footprint "eagle-import:R0603")
      (libsource (lib "eagle-import") (part "R-US_R0603"))
    )
    (comp (ref "R36")
      (value "18K")
      (footprint "eagle-import:R0603")
      (libsource (lib "eagle-import") (part "R-US_R0603"))
    )
    (comp (ref "R37")
      (value "66K5")
      (footprint "eagle-import:R0603")
      (libsource (lib "eagle-import") (part "R-US_R0603"))
    )
    (comp (ref "R38")
      (value "39K")
      (footprint "eagle-import:R0603")
      (libsource (lib "eagle-import") (part "R-US_R0603"))
    )
    (comp (ref "R39")
      (value "100R")
      (footprint "eagle-import:R0603")
      (libsource (lib "eagle-import") (part "R-US_R0603"))
    )
    (comp (ref "R40")
      (value "39K")
      (footprint "eagle-import:R0603")
      (libsource (lib "eagle-import") (part "R-US_R0603"))
    )
    (comp (ref "R41")
      (value "66K5")
      (footprint "eagle-import:R0603")
      (libsource (lib "eagle-import") (part "R-US_R0603"))
    )
    (comp (ref "R42")
      (value "18K")
      (footprint "eagle-import:R0603")
      (libsource (lib "eagle-import") (part "R-US_R0603"))
    )
    (comp (ref "R43")
      (value "18K")
      (footprint "eagle-import:R0603")
      (libsource (lib "eagle-import") (part "R-US_R0603"))
    )
    (comp (ref "R44")
      (value "66K5")
      (footprint "eagle-import:R0603")
      (libsource (lib "eagle-import") (part "R-US_R0603"))
    )
    (comp (ref "R45")
      (value "39K")
      (footprint "eagle-import:R0603")
      (libsource (lib "eagle-import") (part "R-US_R0603"))
    )
    (comp (ref "R64")
      (value "100R")
      (footprint "eagle-import:R0603")
      (libsource (lib "eagle-import") (part "R-US_R0603"))
    )
    (comp (ref "R65")
      (value "39K")
      (footprint "eagle-import:R0603")
      (libsource (lib "eagle-import") (part "R-US_R0603"))
    )
    (comp (ref "U2")
      (value "PCM3060")
      (footprint "eagle-import:TSSOP-28")
      (libsource (lib "eagle-import") (part "PCM3060PWR"))
    )
    (comp (ref "U14")
      (value "LD1117-5V")
      (footprint "eagle-import:SOT223")
      (libsource (lib "eagle-import") (part "LD1117-5V"))
    )
  )
  (nets
    (net (code "1") (name "+3V3_A") (class "Default")
      (node (ref "C48") (pin "1") (pinfunction "1_1") (pintype "passive"))
      (node (ref "C62") (pin "1") (pinfunction "1_1") (pintype "passive"))
      (node (ref "U4") (pin "16") (pinfunction "VCC_16") (pintype "power_in"))
      (node (ref "U6") (pin "4") (pinfunction "V+_4") (pintype "power_in"))
      (node (ref "U9") (pin "A5") (pinfunction "3V3_A_A5") (pintype "bidirectional"))
      (node (ref "VR_1") (pin "3") (pinfunction "3_3") (pintype "passive"))
      (node (ref "VR_2") (pin "3") (pinfunction "3_3") (pintype "passive"))
      (node (ref "VR_3") (pin "3") (pinfunction "3_3") (pintype "passive"))
      (node (ref "VR_4") (pin "3") (pinfunction "3_3") (pintype "passive"))
    )
    (net (code "2") (name "+3V3_D") (class "Default")
      (node (ref "C66") (pin "1") (pinfunction "1_1") (pintype "passive"))
      (node (ref "R1") (pin "2") (pinfunction "2_2") (pintype "passive"))
      (node (ref "R111") (pin "2") (pinfunction "2_2") (pintype "passive"))
      (node (ref "R112") (pin "2") (pinfunction "2_2") (pintype "passive"))
      (node (ref "R3") (pin "2") (pinfunction "2_2") (pintype "passive"))
      (node (ref "R4") (pin "2") (pinfunction "2_2") (pintype "passive"))
      (node (ref "R50") (pin "2") (pinfunction "2_2") (pintype "passive"))
      (node (ref "R51") (pin "2") (pinfunction "2_2") (pintype "passive"))
      (node (ref "R52") (pin "2") (pinfunction "2_2") (pintype "passive"))
      (node (ref "R53") (pin "2") (pinfunction "2_2") (pintype "passive"))
      (node (ref "R54") (pin "2") (pinfunction "2_2") (pintype "passive"))
      (node (ref "R72") (pin "2") (pinfunction "2_2") (pintype "passive"))
      (node (ref "U15") (pin "6") (pinfunction "V_6") (pintype "bidirectional"))
      (node (ref "U2") (pin "15") (pinfunction "~{RST}_15") (pintype "bidirectional"))
      (node (ref "U7") (pin "P$4") (pinfunction "VCC_P$4") (pintype "bidirectional"))
      (node (ref "U9") (pin "A3") (pinfunction "3V3_D_A3") (pintype "bidirectional"))
      (node (ref "U9") (pin "A4") (pinfunction "3V3_D_A4") (pintype "bidirectional"))
    )
    (net (code "3") (name "+3V3_SWITCHING") (class "Default")
      (node (ref "C38") (pin "1") (pinfunction "1_1") (pintype "passive"))
      (node (ref "L1") (pin "2") (pinfunction "P$1_2") (pintype "bidirectional"))
      (node (ref "R88") (pin "2") (pinfunction "2_2") (pintype "passive"))
      (node (ref "U_OLED") (pin "2") (pinfunction "VCC_2") (pintype "bidirectional"))
    )
    (net (code "4") (name "+5V") (class "Default")
      (node (ref "C10") (pin "1") (pinfunction "1_1") (pintype "passive"))
      (node (ref "C6") (pin "1") (pinfunction "1_1") (pintype "passive"))
      (node (ref "C60") (pin "1") (pinfunction "1_1") (pintype "passive"))
      (node (ref "FB5") (pin "2") (pinfunction "2_2") (pintype "passive"))
      (node (ref "U2") (pin "24") (pinfunction "VCC_24") (pintype "bidirectional"))
    )
    (net (code "5") (name "+12V") (class "Default")
      (node (ref "C1") (pin "1") (pinfunction "1_1") (pintype "passive"))
      (node (ref "C27") (pin "1") (pinfunction "1_1") (pintype "passive"))
      (node (ref "C29") (pin "1") (pinfunction "1_1") (pintype "passive"))
      (node (ref "C36") (pin "1") (pinfunction "1_1") (pintype "passive"))
      (node (ref "C47") (pin "1") (pinfunction "1_1") (pintype "passive"))
      (node (ref "C49") (pin "1") (pinfunction "1_1") (pintype "passive"))
      (node (ref "C51") (pin "1") (pinfunction "1_1") (pintype "passive"))
      (node (ref "C58") (pin "1") (pinfunction "1_1") (pintype "passive"))
      (node (ref "D5") (pin "C") (pinfunction "C_C") (pintype "passive"))
      (node (ref "FB1") (pin "1") (pinfunction "1_1") (pintype "passive"))
      (node (ref "FB2") (pin "1") (pinfunction "1_1") (pintype "passive"))
      (node (ref "U1") (pin "4") (pinfunction "V+_4") (pintype "power_in"))
      (node (ref "U11") (pin "4") (pinfunction "V+_4") (pintype "power_in"))
      (node (ref "U16") (pin "4") (pinfunction "V+_4") (pintype "power_in"))
      (node (ref "U3") (pin "4") (pinfunction "V+_4") (pintype "power_in"))
      (node (ref "U9") (pin "A1") (pinfunction "VIN_A1") (pintype "bidirectional"))
      (node (ref "U9") (pin "A2") (pinfunction "VIN_A2") (pintype "bidirectional"))
    )
    (net (code "6") (name "-10V_REF") (class "Default")
      (node (ref "C40") (pin "1") (pinfunction "1_1") (pintype "passive"))
      (node (ref "R55") (pin "1") (pinfunction "1_1") (pintype "passive"))
      (node (ref "R59") (pin "1") (pinfunction "1_1") (pintype "passive"))
      (node (ref "R62") (pin "1") (pinfunction "1_1") (pintype "passive"))
      (node (ref "R67") (pin "1") (pinfunction "1_1") (pintype "passive"))
      (node (ref "U8") (pin "2") (pinfunction "A_2") (pintype "passive"))
    )
    (net (code "7") (name "-12V") (class "Default")
      (node (ref "C14") (pin "2") (pinfunction "2_2") (pintype "passive"))
      (node (ref "C2") (pin "2") (pinfunction "2_2") (pintype "passive"))
      (node (ref "C43") (pin "2") (pinfunction "2_2") (pintype "passive"))
      (node (ref "C50") (pin "2") (pinfunction "2_2") (pintype "passive"))
      (node (ref "C52") (pin "2") (pinfunction "2_2") (pintype "passive"))
      (node (ref "C53") (pin "2") (pinfunction "2_2") (pintype "passive"))
      (node (ref "D6") (pin "A") (pinfunction "A_A") (pintype "passive"))
      (node (ref "R55") (pin "2") (pinfunction "2_2") (pintype "passive"))
      (node (ref "U1") (pin "11") (pinfunction "V-_11") (pintype "power_in"))
      (node (ref "U11") (pin "11") (pinfunction "V-_11") (pintype "power_in"))
      (node (ref "U16") (pin "11") (pinfunction "V-_11") (pintype "power_in"))
      (node (ref "U3") (pin "11") (pinfunction "V-_11") (pintype "power_in"))
    )
    (net (code "8") (name "AUDIO_IN_1") (class "Default")
      (node (ref "C17") (pin "1") (pinfunction "1_1") (pintype "passive"))
      (node (ref "J8") (pin "TIP") (pinfunction "TIP_TIP") (pintype "passive"))
      (node (ref "J9") (pin "NORM") (pinfunction "NORM_NORM") (pintype "passive"))
    )
    (net (code "9") (name "AUDIO_IN_2") (class "Default")
      (node (ref "C20") (pin "1") (pinfunction "1_1") (pintype "passive"))
      (node (ref "J9") (pin "TIP") (pinfunction "TIP_TIP") (pintype "passive"))
    )
    (net (code "10") (name "AUDIO_IN_3") (class "Default")
      (node (ref "C5") (pin "1") (pinfunction "1_1") (pintype "passive"))
      (node (ref "J10") (pin "TIP") (pinfunction "TIP_TIP") (pintype "passive"))
    )
    (net (code "11") (name "AUDIO_IN_4") (class "Default")
      (node (ref "C28") (pin "1") (pinfunction "1_1") (pintype "passive"))
      (node (ref "J11") (pin "TIP") (pinfunction "TIP_TIP") (pintype "passive"))
    )
    (net (code "12") (name "AUDIO_OUT_1") (class "Default")
      (node (ref "J12") (pin "TIP") (pinfunction "TIP_TIP") (pintype "passive"))
      (node (ref "R20") (pin "1") (pinfunction "1_1") (pintype "passive"))
    )
    (net (code "13") (name "AUDIO_OUT_2") (class "Default")
      (node (ref "J13") (pin "TIP") (pinfunction "TIP_TIP") (pintype "passive"))
      (node (ref "R27") (pin "1") (pinfunction "1_1") (pintype "passive"))
    )
    (net (code "14") (name "AUDIO_OUT_3") (class "Default")
      (node (ref "J14") (pin "TIP") (pinfunction "TIP_TIP") (pintype "passive"))
      (node (ref "R39") (pin "1") (pinfunction "1_1") (pintype "passive"))
    )
    (net (code "15") (name "AUDIO_OUT_4") (class "Default")
      (node (ref "J15") (pin "TIP") (pinfunction "TIP_TIP") (pintype "passive"))
      (node (ref "R64") (pin "1") (pinfunction "1_1") (pintype "passive"))
    )
    (net (code "16") (name "CODEC_1_VCOM") (class "Default")
      (node (ref "C16") (pin "2") (pinfunction "2_2") (pintype "passive"))
      (node (ref "C19") (pin "2") (pinfunction "2_2") (pintype "passive"))
      (node (ref "U3") (pin "10") (pinfunction "+IN_10") (pintype "input"))
      (node (ref "U3") (pin "12") (pinfunction "+IN_12") (pintype "input"))
      (node (ref "U9") (pin "D3") (pinfunction "AUDIO_VCOM_D3") (pintype "bidirectional"))
    )
    (net (code "17") (name "CODEC_2_VCOM") (class "Default")
      (node (ref "C11") (pin "1") (pinfunction "1_1") (pintype "passive"))
      (node (ref "C12") (pin "1") (pinfunction "1_1") (pintype "passive"))
      (node (ref "C13") (pin "2") (pinfunction "2_2") (pintype "passive"))
      (node (ref "C4") (pin "2") (pinfunction "2_2") (pintype "passive"))
      (node (ref "U1") (pin "10") (pinfunction "+IN_10") (pintype "input"))
      (node (ref "U1") (pin "12") (pinfunction "+IN_12") (pintype "input"))
      (node (ref "U2") (pin "21") (pinfunction "VCOM_21") (pintype "bidirectional"))
    )
    (net (code "18") (name "CODEC_IN_1") (class "Default")
      (node (ref "R10") (pin "2") (pinfunction "2_2") (pintype "passive"))
      (node (ref "U9") (pin "D1") (pinfunction "AUDIO_IN_L_D1") (pintype "bidirectional"))
    )
    (net (code "19") (name "CODEC_IN_2") (class "Default")
      (node (ref "R13") (pin "2") (pinfunction "2_2") (pintype "passive"))
      (node (ref "U9") (pin "D2") (pinfunction "AUDIO_IN_R_D2") (pintype "bidirectional"))
    )
    (net (code "20") (name "CODEC_IN_3") (class "Default")
      (node (ref "R30") (pin "2") (pinfunction "2_2") (pintype "passive"))
      (node (ref "U2") (pin "25") (pinfunction "VINL_25") (pintype "bidirectional"))
    )
    (net (code "21") (name "CODEC_IN_4") (class "Default")
      (node (ref "R33") (pin "2") (pinfunction "2_2") (pintype "passive"))
      (node (ref "U2") (pin "26") (pinfunction "VINR_26") (pintype "bidirectional"))
    )
    (net (code "22") (name "CODEC_OUT_1+") (class "Default")
      (node (ref "R15") (pin "2") (pinfunction "2_2") (pintype "passive"))
      (node (ref "U9") (pin "D5") (pinfunction "AUDIO_OUT_L+_D5") (pintype "bidirectional"))
    )
    (net (code "23") (name "CODEC_OUT_1-") (class "Default")
      (node (ref "R16") (pin "2") (pinfunction "2_2") (pintype "passive"))
      (node (ref "U9") (pin "D4") (pinfunction "AUDIO_OUT_L-_D4") (pintype "bidirectional"))
    )
    (net (code "24") (name "CODEC_OUT_2+") (class "Default")
      (node (ref "R23") (pin "2") (pinfunction "2_2") (pintype "passive"))
      (node (ref "U9") (pin "D6") (pinfunction "AUDIO_OUT_R+_D6") (pintype "bidirectional"))
    )
    (net (code "25") (name "CODEC_OUT_2-") (class "Default")
      (node (ref "R24") (pin "2") (pinfunction "2_2") (pintype "passive"))
      (node (ref "U9") (pin "D7") (pinfunction "AUDIO_OUT_R-_D7") (pintype "bidirectional"))
    )
    (net (code "26") (name "CODEC_OUT_3+") (class "Default")
      (node (ref "R35") (pin "2") (pinfunction "2_2") (pintype "passive"))
      (node (ref "U2") (pin "20") (pinfunction "VOUTL+_20") (pintype "bidirectional"))
    )
    (net (code "27") (name "CODEC_OUT_3-") (class "Default")
      (node (ref "R36") (pin "2") (pinfunction "2_2") (pintype "passive"))
      (node (ref "U2") (pin "19") (pinfunction "VOUTL-_19") (pintype "bidirectional"))
    )
    (net (code "28") (name "CODEC_OUT_4+") (class "Default")
      (node (ref "R42") (pin "2") (pinfunction "2_2") (pintype "passive"))
      (node (ref "U2") (pin "18") (pinfunction "VOUTR+_18") (pintype "bidirectional"))
    )
    (net (code "29") (name "CODEC_OUT_4-") (class "Default")
      (node (ref "R43") (pin "2") (pinfunction "2_2") (pintype "passive"))
      (node (ref "U2") (pin "17") (pinfunction "VOUTR-_17") (pintype "bidirectional"))
    )
    (net (code "30") (name "CV_1") (class "Default")
      (node (ref "C44") (pin "2") (pinfunction "2_2") (pintype "passive"))
      (node (ref "R58") (pin "2") (pinfunction "2_2") (pintype "passive"))
      (node (ref "U6") (pin "1") (pinfunction "OUT_1") (pintype "output"))
      (node (ref "U9") (pin "C7") (pinfunction "GPIO15(ADC0)-PC0/INP10_C7") (pintype "bidirectional"))
    )
    (net (code "31") (name "CV_1_IN") (class "Default")
      (node (ref "J4") (pin "TIP") (pinfunction "TIP_TIP") (pintype "passive"))
      (node (ref "R60") (pin "1") (pinfunction "1_1") (pintype "passive"))
    )
    (net (code "32") (name "CV_1_OUT") (class "Default")
      (node (ref "J17") (pin "TIP") (pinfunction "TIP_TIP") (pintype "passive"))
      (node (ref "R93") (pin "1") (pinfunction "1_1") (pintype "passive"))
    )
    (net (code "33") (name "CV_2") (class "Default")
      (node (ref "C45") (pin "2") (pinfunction "2_2") (pintype "passive"))
      (node (ref "R61") (pin "2") (pinfunction "2_2") (pintype "passive"))
      (node (ref "U6") (pin "7") (pinfunction "OUT_7") (pintype "output"))
      (node (ref "U9") (pin "C6") (pinfunction "GPIO21(ADC6)-PC4/INP4_C6") (pintype "bidirectional"))
    )
    (net (code "34") (name "CV_2_IN") (class "Default")
      (node (ref "J5") (pin "TIP") (pinfunction "TIP_TIP") (pintype "passive"))
      (node (ref "R63") (pin "1") (pinfunction "1_1") (pintype "passive"))
    )
    (net (code "35") (name "CV_2_OUT") (class "Default")
      (node (ref "J3") (pin "TIP") (pinfunction "TIP_TIP") (pintype "passive"))
      (node (ref "R121") (pin "1") (pinfunction "1_1") (pintype "passive"))
    )
    (net (code "36") (name "CV_3") (class "Default")
      (node (ref "C46") (pin "2") (pinfunction "2_2") (pintype "passive"))
      (node (ref "R66") (pin "2") (pinfunction "2_2") (pintype "passive"))
      (node (ref "U6") (pin "8") (pinfunction "OUT_8") (pintype "output"))
      (node (ref "U9") (pin "C5") (pinfunction "GPIO17(ADC2)-PB1/INP5_C5") (pintype "bidirectional"))
    )
    (net (code "37") (name "CV_3_IN") (class "Default")
      (node (ref "J6") (pin "TIP") (pinfunction "TIP_TIP") (pintype "passive"))
      (node (ref "R68") (pin "1") (pinfunction "1_1") (pintype "passive"))
    )
    (net (code "38") (name "DAC_OUT1") (class "Default")
      (node (ref "R89") (pin "2") (pinfunction "2_2") (pintype "passive"))
      (node (ref "U9") (pin "C8") (pinfunction "GPIO23(ADC8/DAC1)-PA4_C8") (pintype "bidirectional"))
    )
    (net (code "39") (name "DAC_OUT2") (class "Default")
      (node (ref "R71") (pin "2") (pinfunction "2_2") (pintype "passive"))
      (node (ref "U9") (pin "C9") (pinfunction "GPIO22(ADC7/DAC2)-PA5_C9") (pintype "bidirectional"))
    )
    (net (code "40") (name "ENC_A") (class "Default")
      (node (ref "ENC_1") (pin "A") (pinfunction "A_A") (pintype "passive"))
      (node (ref "U9") (pin "C1") (pinfunction "GPIO16(ADC1)-PA3/INP15_C1") (pintype "bidirectional"))
    )
    (net (code "41") (name "ENC_B") (class "Default")
      (node (ref "ENC_1") (pin "B") (pinfunction "B_B") (pintype "passive"))
      (node (ref "U9") (pin "C3") (pinfunction "GPIO20(ADC5)-PC1/INP11_C3") (pintype "bidirectional"))
    )
    (net (code "42") (name "ENC_CLICK") (class "Default")
      (node (ref "ENC_1") (pin "E") (pinfunction "2_E") (pintype "passive"))
      (node (ref "U9") (pin "C2") (pinfunction "GPIO19(ADC4)-PA6/INP3_C2") (pintype "bidirectional"))
    )
    (net (code "43") (name "GATE_IN") (class "Default")
      (node (ref "J16") (pin "TIP") (pinfunction "TIP_TIP") (pintype "passive"))
      (node (ref "R56") (pin "1") (pinfunction "1_1") (pintype "passive"))
    )
    (net (code "44") (name "GATE_IN_MCU") (class "Default")
      (node (ref "R73") (pin "1") (pinfunction "1_1") (pintype "passive"))
      (node (ref "U9") (pin "B7") (pinfunction "GPIO11(I2C1_SCL)-PB8_B7") (pintype "bidirectional"))
    )
    (net (code "45") (name "GND") (class "Default")
      (node (ref "C1") (pin "2") (pinfunction "2_2") (pintype "passive"))
      (node (ref "C10") (pin "2") (pinfunction "2_2") (pintype "passive"))
      (node (ref "C11") (pin "2") (pinfunction "2_2") (pintype "passive"))
      (node (ref "C12") (pin "2") (pinfunction "2_2") (pintype "passive"))
      (node (ref "C13") (pin "1") (pinfunction "1_1") (pintype "passive"))
      (node (ref "C14") (pin "1") (pinfunction "1_1") (pintype "passive"))
      (node (ref "C16") (pin "1") (pinfunction "1_1") (pintype "passive"))
      (node (ref "C19") (pin "1") (pinfunction "1_1") (pintype "passive"))
      (node (ref "C2") (pin "1") (pinfunction "1_1") (pintype "passive"))
      (node (ref "C23") (pin "2") (pinfunction "2_2") (pintype "passive"))
      (node (ref "C26") (pin "2") (pinfunction "2_2") (pintype "passive"))
      (node (ref "C27") (pin "2") (pinfunction "2_2") (pintype "passive"))
      (node (ref "C29") (pin "2") (pinfunction "2_2") (pintype "passive"))
      (node (ref "C32") (pin "2") (pinfunction "2_2") (pintype "passive"))
      (node (ref "C35") (pin "2") (pinfunction "2_2") (pintype "passive"))
      (node (ref "C36") (pin "2") (pinfunction "2_2") (pintype "passive"))
      (node (ref "C37") (pin "2") (pinfunction "2_2") (pintype "passive"))
      (node (ref "C38") (pin "2") (pinfunction "2_2") (pintype "passive"))
      (node (ref "C4") (pin "1") (pinfunction "1_1") (pintype "passive"))
      (node (ref "C40") (pin "2") (pinfunction "2_2") (pintype "passive"))
      (node (ref "C43") (pin "1") (pinfunction "1_1") (pintype "passive"))
      (node (ref "C47") (pin "2") (pinfunction "2_2") (pintype "passive"))
      (node (ref "C48") (pin "2") (pinfunction "2_2") (pintype "passive"))
      (node (ref "C49") (pin "2") (pinfunction "2_2") (pintype "passive"))
      (node (ref "C50") (pin "1") (pinfunction "1_1") (pintype "passive"))
      (node (ref "C51") (pin "2") (pinfunction "2_2") (pintype "passive"))
      (node (ref "C52") (pin "1") (pinfunction "1_1") (pintype "passive"))
      (node (ref "C53") (pin "1") (pinfunction "1_1") (pintype "passive"))
      (node (ref "C57") (pin "2") (pinfunction "2_2") (pintype "passive"))
      (node (ref "C58") (pin "2") (pinfunction "2_2") (pintype "passive"))
      (node (ref "C59") (pin "2") (pinfunction "2_2") (pintype "passive"))
      (node (ref "C6") (pin "2") (pinfunction "2_2") (pintype "passive"))
      (node (ref "C60") (pin "2") (pinfunction "2_2") (pintype "passive"))
      (node (ref "C62") (pin "2") (pinfunction "2_2") (pintype "passive"))
      (node (ref "C66") (pin "2") (pinfunction "2_2") (pintype "passive"))
      (node (ref "C67") (pin "1") (pinfunction "1_1") (pintype "passive"))
      (node (ref "C7") (pin "2") (pinfunction "2_2") (pintype "passive"))
      (node (ref "C70") (pin "1") (pinfunction "1_1") (pintype "passive"))
      (node (ref "C9") (pin "2") (pinfunction "2_2") (pintype "passive"))
      (node (ref "D1") (pin "A") (pinfunction "A_A") (pintype "passive"))
      (node (ref "ENC_1") (pin "C") (pinfunction "C_C") (pintype "passive"))
      (node (ref "ENC_1") (pin "D") (pinfunction "1_D") (pintype "passive"))
      (node (ref "J10") (pin "GND") (pinfunction "GND_GND") (pintype "passive"))
      (node (ref "J11") (pin "GND") (pinfunction "GND_GND") (pintype "passive"))
      (node (ref "J12") (pin "GND") (pinfunction "GND_GND") (pintype "passive"))
      (node (ref "J13") (pin "GND") (pinfunction "GND_GND") (pintype "passive"))
      (node (ref "J14") (pin "GND") (pinfunction "GND_GND") (pintype "passive"))
      (node (ref "J15") (pin "GND") (pinfunction "GND_GND") (pintype "passive"))
      (node (ref "J16") (pin "GND") (pinfunction "GND_GND") (pintype "passive"))
      (node (ref "J17") (pin "GND") (pinfunction "GND_GND") (pintype "passive"))
      (node (ref "J3") (pin "GND") (pinfunction "GND_GND") (pintype "passive"))
      (node (ref "J4") (pin "GND") (pinfunction "GND_GND") (pintype "passive"))
      (node (ref "J5") (pin "GND") (pinfunction "GND_GND") (pintype "passive"))
      (node (ref "J6") (pin "GND") (pinfunction "GND_GND") (pintype "passive"))
      (node (ref "J8") (pin "GND") (pinfunction "GND_GND") (pintype "passive"))
      (node (ref "J9") (pin "GND") (pinfunction "GND_GND") (pintype "passive"))
      (node (ref "P1") (pin "GND1A") (pinfunction "GND_GND1A") (pintype "bidirectional"))
      (node (ref "P1") (pin "GND1B") (pinfunction "GND_GND1B") (pintype "bidirectional"))
      (node (ref "P1") (pin "GND2A") (pinfunction "GND_GND2A") (pintype "bidirectional"))
      (node (ref "P1") (pin "GND2B") (pinfunction "GND_GND2B") (pintype "bidirectional"))
      (node (ref "P1") (pin "GND3A") (pinfunction "GND_GND3A") (pintype "bidirectional"))
      (node (ref "P1") (pin "GND3B") (pinfunction "GND_GND3B") (pintype "bidirectional"))
      (node (ref "Q2") (pin "E") (pinfunction "E_E") (pintype "passive"))
      (node (ref "R2") (pin "2") (pinfunction "2_2") (pintype "passive"))
      (node (ref "R21") (pin "2") (pinfunction "2_2") (pintype "passive"))
      (node (ref "R28") (pin "2") (pinfunction "2_2") (pintype "passive"))
      (node (ref "R40") (pin "2") (pinfunction "2_2") (pintype "passive"))
      (node (ref "R5") (pin "2") (pinfunction "2_2") (pintype "passive"))
      (node (ref "R57") (pin "1") (pinfunction "1_1") (pintype "passive"))
      (node (ref "R65") (pin "2") (pinfunction "2_2") (pintype "passive"))
      (node (ref "R87") (pin "2") (pinfunction "2_2") (pintype "passive"))
      (node (ref "S1") (pin "1") (pinfunction "1_1") (pintype "passive"))
      (node (ref "S1") (pin "2") (pinfunction "2_2") (pintype "passive"))
      (node (ref "SW_TOGGLE") (pin "2") (pinfunction "P_2") (pintype "passive"))
      (node (ref "U11") (pin "10") (pinfunction "+IN_10") (pintype "input"))
      (node (ref "U11") (pin "12") (pinfunction "+IN_12") (pintype "input"))
      (node (ref "U11") (pin "3") (pinfunction "+IN_3") (pintype "input"))
      (node (ref "U11") (pin "5") (pinfunction "+IN_5") (pintype "input"))
      (node (ref "U12") (pin "2") (pinfunction "GND_2") (pintype "passive"))
      (node (ref "U12") (pin "7") (pinfunction "EPAD_7") (pintype "passive"))
      (node (ref "U14") (pin "1") (pinfunction "GND_1") (pintype "input"))
      (node (ref "U15") (pin "5") (pinfunction "GND_5") (pintype "bidirectional"))
      (node (ref "U16") (pin "10") (pinfunction "+IN_10") (pintype "input"))
      (node (ref "U16") (pin "12") (pinfunction "+IN_12") (pintype "input"))
      (node (ref "U16") (pin "3") (pinfunction "+IN_3") (pintype "input"))
      (node (ref "U16") (pin "5") (pinfunction "+IN_5") (pintype "input"))
      (node (ref "U2") (pin "16") (pinfunction "SGND_16") (pintype "bidirectional"))
      (node (ref "U2") (pin "22") (pinfunction "AGND2_22") (pintype "bidirectional"))
      (node (ref "U2") (pin "23") (pinfunction "AGND1_23") (pintype "bidirectional"))
      (node (ref "U2") (pin "27") (pinfunction "MS/ADR/IFMD_27") (pintype "bidirectional"))
      (node (ref "U2") (pin "8") (pinfunction "DGND_8") (pintype "bidirectional"))
      (node (ref "U4") (pin "1") (pinfunction "X4_1") (pintype "bidirectional"))
      (node (ref "U4") (pin "2") (pinfunction "X6_2") (pintype "bidirectional"))
      (node (ref "U4") (pin "4") (pinfunction "X7_4") (pintype "bidirectional"))
      (node (ref "U4") (pin "5") (pinfunction "X5_5") (pintype "bidirectional"))
      (node (ref "U4") (pin "6") (pinfunction "INH_6") (pintype "input"))
      (node (ref "U4") (pin "7") (pinfunction "VEE_7") (pintype "power_in"))
      (node (ref "U4") (pin "8") (pinfunction "GND_8") (pintype "power_in"))
      (node (ref "U4") (pin "9") (pinfunction "C_9") (pintype "input"))
      (node (ref "U6") (pin "10") (pinfunction "+IN_10") (pintype "input"))
      (node (ref "U6") (pin "11") (pinfunction "V-_11") (pintype "power_in"))
      (node (ref "U6") (pin "12") (pinfunction "+IN_12") (pintype "input"))
      (node (ref "U6") (pin "3") (pinfunction "+IN_3") (pintype "input"))
      (node (ref "U6") (pin "5") (pinfunction "+IN_5") (pintype "input"))
      (node (ref "U7") (pin "GND1") (pinfunction "SHIELD_GND1") (pintype "bidirectional"))
      (node (ref "U7") (pin "GND2") (pinfunction "SHIELD_GND2") (pintype "bidirectional"))
      (node (ref "U7") (pin "P$6") (pinfunction "GND_P$6") (pintype "bidirectional"))
      (node (ref "U8") (pin "1") (pinfunction "C_1") (pintype "passive"))
      (node (ref "U9") (pin "A10") (pinfunction "GND_A10") (pintype "bidirectional"))
      (node (ref "U9") (pin "A6") (pinfunction "GND_A6") (pintype "bidirectional"))
      (node (ref "U9") (pin "A7") (pinfunction "GND_A7") (pintype "bidirectional"))
      (node (ref "U9") (pin "A8") (pinfunction "GND_A8") (pintype "bidirectional"))
      (node (ref "U9") (pin "A9") (pinfunction "GND_A9") (pintype "bidirectional"))
      (node (ref "U_OLED") (pin "1") (pinfunction "GND_1") (pintype "bidirectional"))
      (node (ref "VR_1") (pin "1") (pinfunction "1_1") (pintype "passive"))
      (node (ref "VR_2") (pin "1") (pinfunction "1_1") (pintype "passive"))
      (node (ref "VR_3") (pin "1") (pinfunction "1_1") (pintype "passive"))
      (node (ref "VR_4") (pin "1") (pinfunction "1_1") (pintype "passive"))
    )
    (net (code "46") (name "KNOB_1") (class "Default")
      (node (ref "U4") (pin "13") (pinfunction "X0_13") (pintype "bidirectional"))
      (node (ref "VR_1") (pin "2") (pinfunction "2_2") (pintype "passive"))
    )
    (net (code "47") (name "KNOB_2") (class "Default")
      (node (ref "U4") (pin "14") (pinfunction "X1_14") (pintype "bidirectional"))
      (node (ref "VR_2") (pin "2") (pinfunction "2_2") (pintype "passive"))
    )
    (net (code "48") (name "KNOB_3") (class "Default")
      (node (ref "U4") (pin "15") (pinfunction "X2_15") (pintype "bidirectional"))
      (node (ref "VR_3") (pin "2") (pinfunction "2_2") (pintype "passive"))
    )
    (net (code "49") (name "KNOB_4") (class "Default")
      (node (ref "U4") (pin "12") (pinfunction "X3_12") (pintype "bidirectional"))
      (node (ref "VR_4") (pin "2") (pinfunction "2_2") (pintype "passive"))
    )
    (net (code "50") (name "KNOB_MUX") (class "Default")
      (node (ref "U4") (pin "3") (pinfunction "X_3") (pintype "bidirectional"))
      (node (ref "U9") (pin "C4") (pinfunction "GPIO18(ADC3)-PA7/INP7_C4") (pintype "bidirectional"))
    )
    (net (code "51") (name "MIDI_IN_RING") (class "Default")
      (node (ref "J18") (pin "RING") (pinfunction "NORM_RING") (pintype "passive"))
      (node (ref "R114") (pin "1") (pinfunction "1_1") (pintype "passive"))
      (node (ref "R117") (pin "1") (pinfunction "1_1") (pintype "passive"))
    )
    (net (code "52") (name "MIDI_IN_TIP") (class "Default")
      (node (ref "J18") (pin "TIP") (pinfunction "TIP_TIP") (pintype "passive"))
      (node (ref "R115") (pin "1") (pinfunction "1_1") (pintype "passive"))
      (node (ref "R116") (pin "1") (pinfunction "1_1") (pintype "passive"))
    )
    (net (code "53") (name "MIDI_RX") (class "Default")
      (node (ref "R111") (pin "1") (pinfunction "1_1") (pintype "passive"))
      (node (ref "U15") (pin "4") (pinfunction "OUT_4") (pintype "bidirectional"))
      (node (ref "U9") (pin "B5") (pinfunction "GPIO14(USART1_RX)-PB7_B5") (pintype "bidirectional"))
    )
    (net (code "54") (name "MIDI_TX") (class "Default")
      (node (ref "R113") (pin "2") (pinfunction "2_2") (pintype "passive"))
      (node (ref "U9") (pin "B3") (pinfunction "GPIO13(USART1_TX)-PB6_B3") (pintype "bidirectional"))
    )
    (net (code "55") (name "MUX_CTRL_A") (class "Default")
      (node (ref "U4") (pin "11") (pinfunction "A_11") (pintype "input"))
      (node (ref "U9") (pin "B8") (pinfunction "GPIO12(I2C1_SDA)-PB9_B8") (pintype "bidirectional"))
    )
    (net (code "56") (name "MUX_CTRL_B") (class "Default")
      (node (ref "U4") (pin "10") (pinfunction "B_10") (pintype "input"))
      (node (ref "U9") (pin "C10") (pinfunction "GPIO31(ADC12/SPI2_MISO)-PC2_C10") (pintype "bidirectional"))
    )
    (net (code "57") (name "Net-(C5-Pad2)") (class "Default")
      (node (ref "C5") (pin "2") (pinfunction "2_2") (pintype "passive"))
      (node (ref "R19") (pin "2") (pinfunction "2_2") (pintype "passive"))
    )
    (net (code "58") (name "Net-(C17-Pad2)") (class "Default")
      (node (ref "C17") (pin "2") (pinfunction "2_2") (pintype "passive"))
      (node (ref "R8") (pin "2") (pinfunction "2_2") (pintype "passive"))
    )
    (net (code "59") (name "Net-(C20-Pad2)") (class "Default")
      (node (ref "C20") (pin "2") (pinfunction "2_2") (pintype "passive"))
      (node (ref "R11") (pin "2") (pinfunction "2_2") (pintype "passive"))
    )
    (net (code "60") (name "Net-(C21-Pad1)") (class "Default")
      (node (ref "C21") (pin "1") (pinfunction "1_1") (pintype "passive"))
      (node (ref "R16") (pin "1") (pinfunction "1_1") (pintype "passive"))
      (node (ref "R17") (pin "2") (pinfunction "2_2") (pintype "passive"))
      (node (ref "R21") (pin "1") (pinfunction "1_1") (pintype "passive"))
    )
    (net (code "61") (name "Net-(C21-Pad2)") (class "Default")
      (node (ref "C21") (pin "2") (pinfunction "2_2") (pintype "passive"))
      (node (ref "R14") (pin "2") (pinfunction "2_2") (pintype "passive"))
      (node (ref "R15") (pin "1") (pinfunction "1_1") (pintype "passive"))
      (node (ref "R18") (pin "2") (pinfunction "2_2") (pintype "passive"))
    )
    (net (code "62") (name "Net-(C24-Pad1)") (class "Default")
      (node (ref "C24") (pin "1") (pinfunction "1_1") (pintype "passive"))
      (node (ref "R24") (pin "1") (pinfunction "1_1") (pintype "passive"))
      (node (ref "R25") (pin "2") (pinfunction "2_2") (pintype "passive"))
      (node (ref "R28") (pin "1") (pinfunction "1_1") (pintype "passive"))
    )
    (net (code "63") (name "Net-(C24-Pad2)") (class "Default")
      (node (ref "C24") (pin "2") (pinfunction "2_2") (pintype "passive"))
      (node (ref "R22") (pin "2") (pinfunction "2_2") (pintype "passive"))
      (node (ref "R23") (pin "1") (pinfunction "1_1") (pintype "passive"))
      (node (ref "R26") (pin "2") (pinfunction "2_2") (pintype "passive"))
    )
    (net (code "64") (name "Net-(C28-Pad2)") (class "Default")
      (node (ref "C28") (pin "2") (pinfunction "2_2") (pintype "passive"))
      (node (ref "R31") (pin "2") (pinfunction "2_2") (pintype "passive"))
    )
    (net (code "65") (name "Net-(C30-Pad1)") (class "Default")
      (node (ref "C30") (pin "1") (pinfunction "1_1") (pintype "passive"))
      (node (ref "R36") (pin "1") (pinfunction "1_1") (pintype "passive"))
      (node (ref "R37") (pin "2") (pinfunction "2_2") (pintype "passive"))
      (node (ref "R40") (pin "1") (pinfunction "1_1") (pintype "passive"))
    )
    (net (code "66") (name "Net-(C30-Pad2)") (class "Default")
      (node (ref "C30") (pin "2") (pinfunction "2_2") (pintype "passive"))
      (node (ref "R34") (pin "2") (pinfunction "2_2") (pintype "passive"))
      (node (ref "R35") (pin "1") (pinfunction "1_1") (pintype "passive"))
      (node (ref "R38") (pin "2") (pinfunction "2_2") (pintype "passive"))
    )
    (net (code "67") (name "Net-(C33-Pad1)") (class "Default")
      (node (ref "C33") (pin "1") (pinfunction "1_1") (pintype "passive"))
      (node (ref "R43") (pin "1") (pinfunction "1_1") (pintype "passive"))
      (node (ref "R44") (pin "2") (pinfunction "2_2") (pintype "passive"))
      (node (ref "R65") (pin "1") (pinfunction "1_1") (pintype "passive"))
    )
    (net (code "68") (name "Net-(C33-Pad2)") (class "Default")
      (node (ref "C33") (pin "2") (pinfunction "2_2") (pintype "passive"))
      (node (ref "R41") (pin "2") (pinfunction "2_2") (pintype "passive"))
      (node (ref "R42") (pin "1") (pinfunction "1_1") (pintype "passive"))
      (node (ref "R45") (pin "2") (pinfunction "2_2") (pintype "passive"))
    )
    (net (code "69") (name "Net-(C67-Pad2)") (class "Default")
      (node (ref "C67") (pin "2") (pinfunction "2_2") (pintype "passive"))
      (node (ref "J18") (pin "GND") (pinfunction "GND_GND") (pintype "passive"))
    )
    (net (code "70") (name "Net-(C70-Pad2)") (class "Default")
      (node (ref "C70") (pin "2") (pinfunction "2_2") (pintype "passive"))
      (node (ref "J19") (pin "GND") (pinfunction "GND_GND") (pintype "passive"))
    )
    (net (code "71") (name "Net-(D5-PadA)") (class "Default")
      (node (ref "D5") (pin "A") (pinfunction "A_A") (pintype "passive"))
      (node (ref "FB3") (pin "2") (pinfunction "2_2") (pintype "passive"))
    )
    (net (code "72") (name "Net-(D6-PadC)") (class "Default")
      (node (ref "D6") (pin "C") (pinfunction "C_C") (pintype "passive"))
      (node (ref "FB4") (pin "2") (pinfunction "2_2") (pintype "passive"))
    )
    (net (code "73") (name "Net-(FB3-Pad1)") (class "Default")
      (node (ref "FB3") (pin "1") (pinfunction "1_1") (pintype "passive"))
      (node (ref "P1") (pin "P12VA") (pinfunction "+12VIN_P12VA") (pintype "bidirectional"))
      (node (ref "P1") (pin "P12VB") (pinfunction "+12VIN_P12VB") (pintype "bidirectional"))
    )
    (net (code "74") (name "Net-(FB4-Pad1)") (class "Default")
      (node (ref "FB4") (pin "1") (pinfunction "1_1") (pintype "passive"))
      (node (ref "P1") (pin "N12VA") (pinfunction "-12VIN_N12VA") (pintype "bidirectional"))
      (node (ref "P1") (pin "N12VB") (pinfunction "-12VIN_N12VB") (pintype "bidirectional"))
    )
    (net (code "75") (name "Net-(J19-NORM)") (class "Default")
      (node (ref "J19") (pin "RING") (pinfunction "NORM_RING") (pintype "passive"))
      (node (ref "R112") (pin "1") (pinfunction "1_1") (pintype "passive"))
    )
    (net (code "76") (name "Net-(J19-PadTIP)") (class "Default")
      (node (ref "J19") (pin "TIP") (pinfunction "TIP_TIP") (pintype "passive"))
      (node (ref "R113") (pin "1") (pinfunction "1_1") (pintype "passive"))
    )
    (net (code "77") (name "Net-(L1-P$2)") (class "Default")
      (node (ref "D1") (pin "C") (pinfunction "C_C") (pintype "passive"))
      (node (ref "L1") (pin "1") (pinfunction "P$2_1") (pintype "bidirectional"))
      (node (ref "U12") (pin "3") (pinfunction "SW_3") (pintype "passive"))
    )
    (net (code "78") (name "Net-(Q2-PadB)") (class "Default")
      (node (ref "Q2") (pin "B") (pinfunction "B_B") (pintype "passive"))
      (node (ref "R56") (pin "2") (pinfunction "2_2") (pintype "passive"))
      (node (ref "R57") (pin "2") (pinfunction "2_2") (pintype "passive"))
    )
    (net (code "79") (name "Net-(Q2-PadC)") (class "Default")
      (node (ref "Q2") (pin "C") (pinfunction "C_C") (pintype "passive"))
      (node (ref "R72") (pin "1") (pinfunction "1_1") (pintype "passive"))
      (node (ref "R73") (pin "2") (pinfunction "2_2") (pintype "passive"))
    )
    (net (code "80") (name "Net-(R6-Pad2)") (class "Default")
      (node (ref "R6") (pin "2") (pinfunction "2_2") (pintype "passive"))
      (node (ref "R7") (pin "2") (pinfunction "2_2") (pintype "passive"))
    )
    (net (code "81") (name "Net-(R110-Pad1)") (class "Default")
      (node (ref "R110") (pin "1") (pinfunction "1_1") (pintype "passive"))
      (node (ref "R114") (pin "2") (pinfunction "2_2") (pintype "passive"))
      (node (ref "R115") (pin "2") (pinfunction "2_2") (pintype "passive"))
    )
    (net (code "82") (name "Net-(U1A-+IN)") (class "Default")
      (node (ref "C35") (pin "1") (pinfunction "1_1") (pintype "passive"))
      (node (ref "R44") (pin "1") (pinfunction "1_1") (pintype "passive"))
      (node (ref "U1") (pin "3") (pinfunction "+IN_3") (pintype "input"))
    )
    (net (code "83") (name "Net-(U1A--IN)") (class "Default")
      (node (ref "C34") (pin "2") (pinfunction "2_2") (pintype "passive"))
      (node (ref "R41") (pin "1") (pinfunction "1_1") (pintype "passive"))
      (node (ref "U1") (pin "2") (pinfunction "-IN_2") (pintype "input"))
    )
    (net (code "84") (name "Net-(U1A-OUT)") (class "Default")
      (node (ref "C34") (pin "1") (pinfunction "1_1") (pintype "passive"))
      (node (ref "R45") (pin "1") (pinfunction "1_1") (pintype "passive"))
      (node (ref "R64") (pin "2") (pinfunction "2_2") (pintype "passive"))
      (node (ref "U1") (pin "1") (pinfunction "OUT_1") (pintype "output"))
    )
    (net (code "85") (name "Net-(U1B-+IN)") (class "Default")
      (node (ref "C32") (pin "1") (pinfunction "1_1") (pintype "passive"))
      (node (ref "R37") (pin "1") (pinfunction "1_1") (pintype "passive"))
      (node (ref "U1") (pin "5") (pinfunction "+IN_5") (pintype "input"))
    )
    (net (code "86") (name "Net-(U1B--IN)") (class "Default")
      (node (ref "C31") (pin "2") (pinfunction "2_2") (pintype "passive"))
      (node (ref "R34") (pin "1") (pinfunction "1_1") (pintype "passive"))
      (node (ref "U1") (pin "6") (pinfunction "-IN_6") (pintype "input"))
    )
    (net (code "87") (name "Net-(U1B-OUT)") (class "Default")
      (node (ref "C31") (pin "1") (pinfunction "1_1") (pintype "passive"))
      (node (ref "R38") (pin "1") (pinfunction "1_1") (pintype "passive"))
      (node (ref "R39") (pin "2") (pinfunction "2_2") (pintype "passive"))
      (node (ref "U1") (pin "7") (pinfunction "OUT_7") (pintype "output"))
    )
    (net (code "88") (name "Net-(U1C--IN)") (class "Default")
      (node (ref "C3") (pin "2") (pinfunction "2_2") (pintype "passive"))
      (node (ref "R19") (pin "1") (pinfunction "1_1") (pintype "passive"))
      (node (ref "R29") (pin "2") (pinfunction "2_2") (pintype "passive"))
      (node (ref "U1") (pin "9") (pinfunction "-IN_9") (pintype "input"))
    )
    (net (code "89") (name "Net-(U1C-OUT)") (class "Default")
      (node (ref "C3") (pin "1") (pinfunction "1_1") (pintype "passive"))
      (node (ref "R29") (pin "1") (pinfunction "1_1") (pintype "passive"))
      (node (ref "R30") (pin "1") (pinfunction "1_1") (pintype "passive"))
      (node (ref "U1") (pin "8") (pinfunction "OUT_8") (pintype "output"))
    )
    (net (code "90") (name "Net-(U1D--IN)") (class "Default")
      (node (ref "C8") (pin "2") (pinfunction "2_2") (pintype "passive"))
      (node (ref "R31") (pin "1") (pinfunction "1_1") (pintype "passive"))
      (node (ref "R32") (pin "2") (pinfunction "2_2") (pintype "passive"))
      (node (ref "U1") (pin "13") (pinfunction "-IN_13") (pintype "input"))
    )
    (net (code "91") (name "Net-(U1D-OUT)") (class "Default")
      (node (ref "C8") (pin "1") (pinfunction "1_1") (pintype "passive"))
      (node (ref "R32") (pin "1") (pinfunction "1_1") (pintype "passive"))
      (node (ref "R33") (pin "1") (pinfunction "1_1") (pintype "passive"))
      (node (ref "U1") (pin "14") (pinfunction "OUT_14") (pintype "output"))
    )
    (net (code "92") (name "Net-(U2-MC{slash}SCL{slash}FMT)") (class "Default")
      (node (ref "R3") (pin "1") (pinfunction "1_1") (pintype "passive"))
      (node (ref "R6") (pin "1") (pinfunction "1_1") (pintype "passive"))
      (node (ref "U2") (pin "1") (pinfunction "MC/SCL/FMT_1") (pintype "bidirectional"))
    )
    (net (code "93") (name "Net-(U2-MD{slash}SDA{slash}DEMP)") (class "Default")
      (node (ref "R4") (pin "1") (pinfunction "1_1") (pintype "passive"))
      (node (ref "R5") (pin "1") (pinfunction "1_1") (pintype "passive"))
      (node (ref "R7") (pin "1") (pinfunction "1_1") (pintype "passive"))
      (node (ref "U2") (pin "2") (pinfunction "MD/SDA/DEMP_2") (pintype "bidirectional"))
    )
    (net (code "94") (name "Net-(U2-MODE)") (class "Default")
      (node (ref "R2") (pin "1") (pinfunction "1_1") (pintype "passive"))
      (node (ref "U2") (pin "28") (pinfunction "MODE_28") (pintype "bidirectional"))
    )
    (net (code "95") (name "Net-(U2-VDD)") (class "Default")
      (node (ref "C7") (pin "1") (pinfunction "1_1") (pintype "passive"))
      (node (ref "C9") (pin "1") (pinfunction "1_1") (pintype "passive"))
      (node (ref "R1") (pin "1") (pinfunction "1_1") (pintype "passive"))
      (node (ref "U2") (pin "7") (pinfunction "VDD_7") (pintype "bidirectional"))
    )
    (net (code "96") (name "Net-(U3A-+IN)") (class "Default")
      (node (ref "C26") (pin "1") (pinfunction "1_1") (pintype "passive"))
      (node (ref "R25") (pin "1") (pinfunction "1_1") (pintype "passive"))
      (node (ref "U3") (pin "3") (pinfunction "+IN_3") (pintype "input"))
    )
    (net (code "97") (name "Net-(U3A--IN)") (class "Default")
      (node (ref "C25") (pin "2") (pinfunction "2_2") (pintype "passive"))
      (node (ref "R22") (pin "1") (pinfunction "1_1") (pintype "passive"))
      (node (ref "U3") (pin "2") (pinfunction "-IN_2") (pintype "input"))
    )
    (net (code "98") (name "Net-(U3A-OUT)") (class "Default")
      (node (ref "C25") (pin "1") (pinfunction "1_1") (pintype "passive"))
      (node (ref "R26") (pin "1") (pinfunction "1_1") (pintype "passive"))
      (node (ref "R27") (pin "2") (pinfunction "2_2") (pintype "passive"))
      (node (ref "U3") (pin "1") (pinfunction "OUT_1") (pintype "output"))
    )
    (net (code "99") (name "Net-(U3B-+IN)") (class "Default")
      (node (ref "C23") (pin "1") (pinfunction "1_1") (pintype "passive"))
      (node (ref "R17") (pin "1") (pinfunction "1_1") (pintype "passive"))
      (node (ref "U3") (pin "5") (pinfunction "+IN_5") (pintype "input"))
    )
    (net (code "100") (name "Net-(U3B--IN)") (class "Default")
      (node (ref "C22") (pin "2") (pinfunction "2_2") (pintype "passive"))
      (node (ref "R14") (pin "1") (pinfunction "1_1") (pintype "passive"))
      (node (ref "U3") (pin "6") (pinfunction "-IN_6") (pintype "input"))
    )
    (net (code "101") (name "Net-(U3B-OUT)") (class "Default")
      (node (ref "C22") (pin "1") (pinfunction "1_1") (pintype "passive"))
      (node (ref "R18") (pin "1") (pinfunction "1_1") (pintype "passive"))
      (node (ref "R20") (pin "2") (pinfunction "2_2") (pintype "passive"))
      (node (ref "U3") (pin "7") (pinfunction "OUT_7") (pintype "output"))
    )
    (net (code "102") (name "Net-(U3C--IN)") (class "Default")
      (node (ref "C15") (pin "2") (pinfunction "2_2") (pintype "passive"))
      (node (ref "R8") (pin "1") (pinfunction "1_1") (pintype "passive"))
      (node (ref "R9") (pin "2") (pinfunction "2_2") (pintype "passive"))
      (node (ref "U3") (pin "9") (pinfunction "-IN_9") (pintype "input"))
    )
    (net (code "103") (name "Net-(U3C-OUT)") (class "Default")
      (node (ref "C15") (pin "1") (pinfunction "1_1") (pintype "passive"))
      (node (ref "R10") (pin "1") (pinfunction "1_1") (pintype "passive"))
      (node (ref "R9") (pin "1") (pinfunction "1_1") (pintype "passive"))
      (node (ref "U3") (pin "8") (pinfunction "OUT_8") (pintype "output"))
    )
    (net (code "104") (name "Net-(U3D--IN)") (class "Default")
      (node (ref "C18") (pin "2") (pinfunction "2_2") (pintype "passive"))
      (node (ref "R11") (pin "1") (pinfunction "1_1") (pintype "passive"))
      (node (ref "R12") (pin "2") (pinfunction "2_2") (pintype "passive"))
      (node (ref "U3") (pin "13") (pinfunction "-IN_13") (pintype "input"))
    )
    (net (code "105") (name "Net-(U3D-OUT)") (class "Default")
      (node (ref "C18") (pin "1") (pinfunction "1_1") (pintype "passive"))
      (node (ref "R12") (pin "1") (pinfunction "1_1") (pintype "passive"))
      (node (ref "R13") (pin "1") (pinfunction "1_1") (pintype "passive"))
      (node (ref "U3") (pin "14") (pinfunction "OUT_14") (pintype "output"))
    )
    (net (code "106") (name "Net-(U6A--IN)") (class "Default")
      (node (ref "C44") (pin "1") (pinfunction "1_1") (pintype "passive"))
      (node (ref "R58") (pin "1") (pinfunction "1_1") (pintype "passive"))
      (node (ref "R59") (pin "2") (pinfunction "2_2") (pintype "passive"))
      (node (ref "R60") (pin "2") (pinfunction "2_2") (pintype "passive"))
      (node (ref "U6") (pin "2") (pinfunction "-IN_2") (pintype "input"))
    )
    (net (code "107") (name "Net-(U6B--IN)") (class "Default")
      (node (ref "C45") (pin "1") (pinfunction "1_1") (pintype "passive"))
      (node (ref "R61") (pin "1") (pinfunction "1_1") (pintype "passive"))
      (node (ref "R62") (pin "2") (pinfunction "2_2") (pintype "passive"))
      (node (ref "R63") (pin "2") (pinfunction "2_2") (pintype "passive"))
      (node (ref "U6") (pin "6") (pinfunction "-IN_6") (pintype "input"))
    )
    (net (code "108") (name "Net-(U6C--IN)") (class "Default")
      (node (ref "C46") (pin "1") (pinfunction "1_1") (pintype "passive"))
      (node (ref "R66") (pin "1") (pinfunction "1_1") (pintype "passive"))
      (node (ref "R67") (pin "2") (pinfunction "2_2") (pintype "passive"))
      (node (ref "R68") (pin "2") (pinfunction "2_2") (pintype "passive"))
      (node (ref "U6") (pin "9") (pinfunction "-IN_9") (pintype "input"))
    )
    (net (code "109") (name "Net-(U6D--IN)") (class "Default")
      (node (ref "U6") (pin "13") (pinfunction "-IN_13") (pintype "input"))
      (node (ref "U6") (pin "14") (pinfunction "OUT_14") (pintype "output"))
    )
    (net (code "110") (name "Net-(U11A--IN)") (class "Default")
      (node (ref "U11") (pin "1") (pinfunction "OUT_1") (pintype "output"))
      (node (ref "U11") (pin "2") (pinfunction "-IN_2") (pintype "input"))
    )
    (net (code "111") (name "Net-(U11B--IN)") (class "Default")
      (node (ref "C39") (pin "1") (pinfunction "1_1") (pintype "passive"))
      (node (ref "R89") (pin "1") (pinfunction "1_1") (pintype "passive"))
      (node (ref "R90") (pin "2") (pinfunction "2_2") (pintype "passive"))
      (node (ref "U11") (pin "6") (pinfunction "-IN_6") (pintype "input"))
    )
    (net (code "112") (name "Net-(U11B-OUT)") (class "Default")
      (node (ref "C39") (pin "2") (pinfunction "2_2") (pintype "passive"))
      (node (ref "R90") (pin "1") (pinfunction "1_1") (pintype "passive"))
      (node (ref "R95") (pin "2") (pinfunction "2_2") (pintype "passive"))
      (node (ref "U11") (pin "7") (pinfunction "OUT_7") (pintype "output"))
    )
    (net (code "113") (name "Net-(U11C--IN)") (class "Default")
      (node (ref "C41") (pin "1") (pinfunction "1_1") (pintype "passive"))
      (node (ref "R95") (pin "1") (pinfunction "1_1") (pintype "passive"))
      (node (ref "R96") (pin "2") (pinfunction "2_2") (pintype "passive"))
      (node (ref "U11") (pin "9") (pinfunction "-IN_9") (pintype "input"))
    )
    (net (code "114") (name "Net-(U11C-OUT)") (class "Default")
      (node (ref "C41") (pin "2") (pinfunction "2_2") (pintype "passive"))
      (node (ref "R93") (pin "2") (pinfunction "2_2") (pintype "passive"))
      (node (ref "R96") (pin "1") (pinfunction "1_1") (pintype "passive"))
      (node (ref "U11") (pin "8") (pinfunction "OUT_8") (pintype "output"))
    )
    (net (code "115") (name "Net-(U11D--IN)") (class "Default")
      (node (ref "U11") (pin "13") (pinfunction "-IN_13") (pintype "input"))
      (node (ref "U11") (pin "14") (pinfunction "OUT_14") (pintype "output"))
    )
    (net (code "116") (name "Net-(U12-VFB)") (class "Default")
      (node (ref "R87") (pin "1") (pinfunction "1_1") (pintype "passive"))
      (node (ref "R88") (pin "1") (pinfunction "1_1") (pintype "passive"))
      (node (ref "U12") (pin "1") (pinfunction "VFB_1") (pintype "passive"))
    )
    (net (code "117") (name "Net-(U12-VIN_A)") (class "Default")
      (node (ref "C37") (pin "1") (pinfunction "1_1") (pintype "passive"))
      (node (ref "FB1") (pin "2") (pinfunction "2_2") (pintype "passive"))
      (node (ref "U12") (pin "4") (pinfunction "VIN_SW_4") (pintype "passive"))
      (node (ref "U12") (pin "5") (pinfunction "VIN_A_5") (pintype "passive"))
    )
    (net (code "118") (name "Net-(U14-IN)") (class "Default")
      (node (ref "C59") (pin "1") (pinfunction "1_1") (pintype "passive"))
      (node (ref "FB2") (pin "2") (pinfunction "2_2") (pintype "passive"))
      (node (ref "U14") (pin "3") (pinfunction "IN_3") (pintype "input"))
    )
    (net (code "119") (name "Net-(U14-OUT)") (class "Default")
      (node (ref "C57") (pin "1") (pinfunction "1_1") (pintype "passive"))
      (node (ref "FB5") (pin "1") (pinfunction "1_1") (pintype "passive"))
      (node (ref "U14") (pin "2") (pinfunction "OUT_2") (pintype "passive"))
      (node (ref "U14") (pin "TAB") (pinfunction "OUT1_TAB") (pintype "passive"))
    )
    (net (code "120") (name "Net-(U15-A)") (class "Default")
      (node (ref "D2") (pin "C") (pinfunction "C_C") (pintype "passive"))
      (node (ref "R110") (pin "2") (pinfunction "2_2") (pintype "passive"))
      (node (ref "U15") (pin "1") (pinfunction "A_1") (pintype "bidirectional"))
    )
    (net (code "121") (name "Net-(U15-C)") (class "Default")
      (node (ref "D2") (pin "A") (pinfunction "A_A") (pintype "passive"))
      (node (ref "R116") (pin "2") (pinfunction "2_2") (pintype "passive"))
      (node (ref "R117") (pin "2") (pinfunction "2_2") (pintype "passive"))
      (node (ref "U15") (pin "2") (pinfunction "C_2") (pintype "bidirectional"))
    )
    (net (code "122") (name "Net-(U16A--IN)") (class "Default")
      (node (ref "U16") (pin "1") (pinfunction "OUT_1") (pintype "output"))
      (node (ref "U16") (pin "2") (pinfunction "-IN_2") (pintype "input"))
    )
    (net (code "123") (name "Net-(U16B--IN)") (class "Default")
      (node (ref "C71") (pin "1") (pinfunction "1_1") (pintype "passive"))
      (node (ref "R118") (pin "2") (pinfunction "2_2") (pintype "passive"))
      (node (ref "R71") (pin "1") (pinfunction "1_1") (pintype "passive"))
      (node (ref "U16") (pin "6") (pinfunction "-IN_6") (pintype "input"))
    )
    (net (code "124") (name "Net-(U16B-OUT)") (class "Default")
      (node (ref "C71") (pin "2") (pinfunction "2_2") (pintype "passive"))
      (node (ref "R118") (pin "1") (pinfunction "1_1") (pintype "passive"))
      (node (ref "R129") (pin "2") (pinfunction "2_2") (pintype "passive"))
      (node (ref "U16") (pin "7") (pinfunction "OUT_7") (pintype "output"))
    )
    (net (code "125") (name "Net-(U16C--IN)") (class "Default")
      (node (ref "C74") (pin "1") (pinfunction "1_1") (pintype "passive"))
      (node (ref "R129") (pin "1") (pinfunction "1_1") (pintype "passive"))
      (node (ref "R130") (pin "2") (pinfunction "2_2") (pintype "passive"))
      (node (ref "U16") (pin "9") (pinfunction "-IN_9") (pintype "input"))
    )
    (net (code "126") (name "Net-(U16C-OUT)") (class "Default")
      (node (ref "C74") (pin "2") (pinfunction "2_2") (pintype "passive"))
      (node (ref "R121") (pin "2") (pinfunction "2_2") (pintype "passive"))
      (node (ref "R130") (pin "1") (pinfunction "1_1") (pintype "passive"))
      (node (ref "U16") (pin "8") (pinfunction "OUT_8") (pintype "output"))
    )
    (net (code "127") (name "Net-(U16D--IN)") (class "Default")
      (node (ref "U16") (pin "13") (pinfunction "-IN_13") (pintype "input"))
      (node (ref "U16") (pin "14") (pinfunction "OUT_14") (pintype "output"))
    )
    (net (code "128") (name "OLED_CMD") (class "Default")
      (node (ref "U9") (pin "D9") (pinfunction "GPIO0(USB_HS_ID)-PB12_D9") (pintype "bidirectional"))
      (node (ref "U_OLED") (pin "6") (pinfunction "DC_6") (pintype "bidirectional"))
    )
    (net (code "129") (name "OLED_CS") (class "Default")
      (node (ref "U9") (pin "B6") (pinfunction "GPIO7(SPI1_NSS)-PG10_B6") (pintype "bidirectional"))
      (node (ref "U_OLED") (pin "7") (pinfunction "CS_7") (pintype "bidirectional"))
    )
    (net (code "130") (name "OLED_DATA") (class "Default")
      (node (ref "U9") (pin "B4") (pinfunction "GPIO10(SPI1_MOSI)-PB5_B4") (pintype "bidirectional"))
      (node (ref "U_OLED") (pin "4") (pinfunction "SDA_4") (pintype "bidirectional"))
    )
    (net (code "131") (name "OLED_RST") (class "Default")
      (node (ref "U9") (pin "D8") (pinfunction "GPIO32(ADC13/SPI2_MOSI)-PC3_D8") (pintype "bidirectional"))
      (node (ref "U_OLED") (pin "5") (pinfunction "RES_5") (pintype "bidirectional"))
    )
    (net (code "132") (name "OLED_SCK") (class "Default")
      (node (ref "U9") (pin "B2") (pinfunction "GPIO8(SPI1_SCK)-PG11_B2") (pintype "bidirectional"))
      (node (ref "U_OLED") (pin "3") (pinfunction "SCL_3") (pintype "bidirectional"))
    )
    (net (code "133") (name "SAI2_FS") (class "Default")
      (node (ref "U2") (pin "11") (pinfunction "LRCK2_DAC_11") (pintype "bidirectional"))
      (node (ref "U2") (pin "4") (pinfunction "LRCK1_ADC_4") (pintype "bidirectional"))
      (node (ref "U9") (pin "D10") (pinfunction "GPIO27(SAI2_FS_B)-PG9_D10") (pintype "bidirectional"))
    )
    (net (code "134") (name "SAI2_MCLK") (class "Default")
      (node (ref "U2") (pin "6") (pinfunction "SCK1_ADC_6") (pintype "bidirectional"))
      (node (ref "U2") (pin "9") (pinfunction "SCKI2_DAC_9") (pintype "bidirectional"))
      (node (ref "U9") (pin "E1") (pinfunction "GPIO24(ADC9/SAI2_MCLK_B)-PA1_E1") (pintype "bidirectional"))
    )
    (net (code "135") (name "SAI2_SCK") (class "Default")
      (node (ref "U2") (pin "10") (pinfunction "BCK2_DAC_10") (pintype "bidirectional"))
      (node (ref "U2") (pin "5") (pinfunction "BCK1_ADC_5") (pintype "bidirectional"))
      (node (ref "U9") (pin "E4") (pinfunction "GPIO28(ADC11/SAI2_SCK_B)-PA2_E4") (pintype "bidirectional"))
    )
    (net (code "136") (name "SAI2_SD_A") (class "Default")
      (node (ref "U2") (pin "12") (pinfunction "DIN_DAC_12") (pintype "bidirectional"))
      (node (ref "U9") (pin "E3") (pinfunction "GPIO26(SAI2_SD_A)-PD11_E3") (pintype "bidirectional"))
    )
    (net (code "137") (name "SAI2_SD_B") (class "Default")
      (node (ref "U2") (pin "3") (pinfunction "DOUT_ADC_3") (pintype "bidirectional"))
      (node (ref "U9") (pin "E2") (pinfunction "GPIO25(ADC10/SAI2_SD_B)-PA0_E2") (pintype "bidirectional"))
    )
    (net (code "138") (name "SDMMC_CK") (class "Default")
      (node (ref "U7") (pin "P$5") (pinfunction "SCK_P$5") (pintype "bidirectional"))
      (node (ref "U9") (pin "E5") (pinfunction "GPIO6(SDMMC1_CK)-PC12_E5") (pintype "bidirectional"))
    )
    (net (code "139") (name "SDMMC_CMD") (class "Default")
      (node (ref "R52") (pin "1") (pinfunction "1_1") (pintype "passive"))
      (node (ref "U7") (pin "P$3") (pinfunction "CMD/DI_P$3") (pintype "bidirectional"))
      (node (ref "U9") (pin "E6") (pinfunction "GPIO5(SDMMC1_CMD)-PD2_E6") (pintype "bidirectional"))
    )
    (net (code "140") (name "SDMMC_D0") (class "Default")
      (node (ref "R53") (pin "1") (pinfunction "1_1") (pintype "passive"))
      (node (ref "U7") (pin "P$7") (pinfunction "D0/DO_P$7") (pintype "bidirectional"))
      (node (ref "U9") (pin "E7") (pinfunction "GPIO4(SDMMC1_D0)-PC8_E7") (pintype "bidirectional"))
    )
    (net (code "141") (name "SDMMC_D1") (class "Default")
      (node (ref "R54") (pin "1") (pinfunction "1_1") (pintype "passive"))
      (node (ref "U7") (pin "P$8") (pinfunction "D1/RSV_P$8") (pintype "bidirectional"))
      (node (ref "U9") (pin "E8") (pinfunction "GPIO3(SDMMC1_D1)-PC9_E8") (pintype "bidirectional"))
    )
    (net (code "142") (name "SDMMC_D2") (class "Default")
      (node (ref "R50") (pin "1") (pinfunction "1_1") (pintype "passive"))
      (node (ref "U7") (pin "P$1") (pinfunction "D2/NC_P$1") (pintype "bidirectional"))
      (node (ref "U9") (pin "E9") (pinfunction "GPIO2(SDMMC1_D2)-PC10_E9") (pintype "bidirectional"))
    )
    (net (code "143") (name "SDMMC_D3") (class "Default")
      (node (ref "R51") (pin "1") (pinfunction "1_1") (pintype "passive"))
      (node (ref "U7") (pin "P$2") (pinfunction "D3/CS_P$2") (pintype "bidirectional"))
      (node (ref "U9") (pin "E10") (pinfunction "GPIO1(SDMMC1_D3)-PC11_E10") (pintype "bidirectional"))
    )
    (net (code "144") (name "SW_MINI") (class "Default")
      (node (ref "S1") (pin "3") (pinfunction "3_3") (pintype "passive"))
      (node (ref "S1") (pin "4") (pinfunction "4_4") (pintype "passive"))
      (node (ref "U9") (pin "B1") (pinfunction "GPIO9(SPI1_MISO)-PB4_B1") (pintype "bidirectional"))
    )
    (net (code "145") (name "TOGGLE_A") (class "Default")
      (node (ref "SW_TOGGLE") (pin "1") (pinfunction "O_1") (pintype "passive"))
      (node (ref "U9") (pin "B10") (pinfunction "GPIO29(USB_HS_D_-)-PB14_B10") (pintype "bidirectional"))
    )
    (net (code "146") (name "TOGGLE_B") (class "Default")
      (node (ref "SW_TOGGLE") (pin "3") (pinfunction "S_3") (pintype "passive"))
      (node (ref "U9") (pin "B9") (pinfunction "GPIO30(USB_HS_D_+)-PB15_B9") (pintype "bidirectional"))
    )
    (net (code "147") (name "unconnected-(J3-PadNORM)") (class "Default")
      (node (ref "J3") (pin "NORM") (pinfunction "NORM_NORM") (pintype "passive"))
    )
    (net (code "148") (name "unconnected-(J4-PadNORM)") (class "Default")
      (node (ref "J4") (pin "NORM") (pinfunction "NORM_NORM") (pintype "passive"))
    )
    (net (code "149") (name "unconnected-(J5-PadNORM)") (class "Default")
      (node (ref "J5") (pin "NORM") (pinfunction "NORM_NORM") (pintype "passive"))
    )
    (net (code "150") (name "unconnected-(J6-PadNORM)") (class "Default")
      (node (ref "J6") (pin "NORM") (pinfunction "NORM_NORM") (pintype "passive"))
    )
    (net (code "151") (name "unconnected-(J8-PadNORM)") (class "Default")
      (node (ref "J8") (pin "NORM") (pinfunction "NORM_NORM") (pintype "passive"))
    )
    (net (code "152") (name "unconnected-(J10-PadNORM)") (class "Default")
      (node (ref "J10") (pin "NORM") (pinfunction "NORM_NORM") (pintype "passive"))
    )
    (net (code "153") (name "unconnected-(J11-PadNORM)") (class "Default")
      (node (ref "J11") (pin "NORM") (pinfunction "NORM_NORM") (pintype "passive"))
    )
    (net (code "154") (name "unconnected-(J12-PadNORM)") (class "Default")
      (node (ref "J12") (pin "NORM") (pinfunction "NORM_NORM") (pintype "passive"))
    )
    (net (code "155") (name "unconnected-(J13-PadNORM)") (class "Default")
      (node (ref "J13") (pin "NORM") (pinfunction "NORM_NORM") (pintype "passive"))
    )
    (net (code "156") (name "unconnected-(J14-PadNORM)") (class "Default")
      (node (ref "J14") (pin "NORM") (pinfunction "NORM_NORM") (pintype "passive"))
    )
    (net (code "157") (name "unconnected-(J15-PadNORM)") (class "Default")
      (node (ref "J15") (pin "NORM") (pinfunction "NORM_NORM") (pintype "passive"))
    )
    (net (code "158") (name "unconnected-(J16-PadNORM)") (class "Default")
      (node (ref "J16") (pin "NORM") (pinfunction "NORM_NORM") (pintype "passive"))
    )
    (net (code "159") (name "unconnected-(J17-PadNORM)") (class "Default")
      (node (ref "J17") (pin "NORM") (pinfunction "NORM_NORM") (pintype "passive"))
    )
    (net (code "160") (name "unconnected-(U2-ZEROL-Pad14)") (class "Default")
      (node (ref "U2") (pin "14") (pinfunction "ZEROL_14") (pintype "bidirectional"))
    )
    (net (code "161") (name "unconnected-(U2-ZEROR-Pad13)") (class "Default")
      (node (ref "U2") (pin "13") (pinfunction "ZEROR_13") (pintype "bidirectional"))
    )
    (net (code "162") (name "unconnected-(U12-N.C.-Pad6)") (class "Default")
      (node (ref "U12") (pin "6") (pinfunction "N.C._6") (pintype "no_connect"))
    )
  )
)
